# CM5_Adapter.net
KiCad netlist of a schematic drawn in Altium Designer
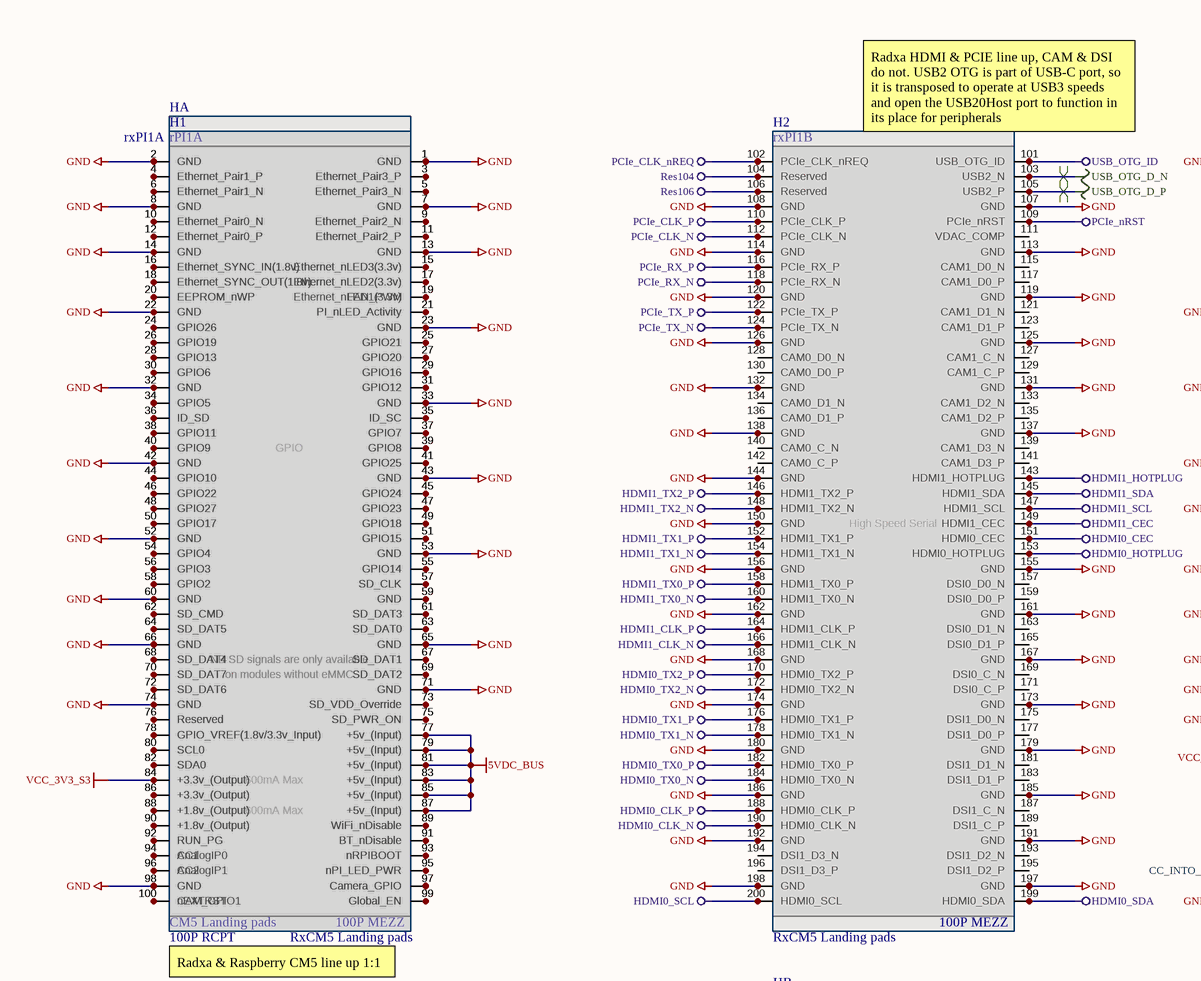
[diagram p0: CM5 Adapter.SchDoc, top left]
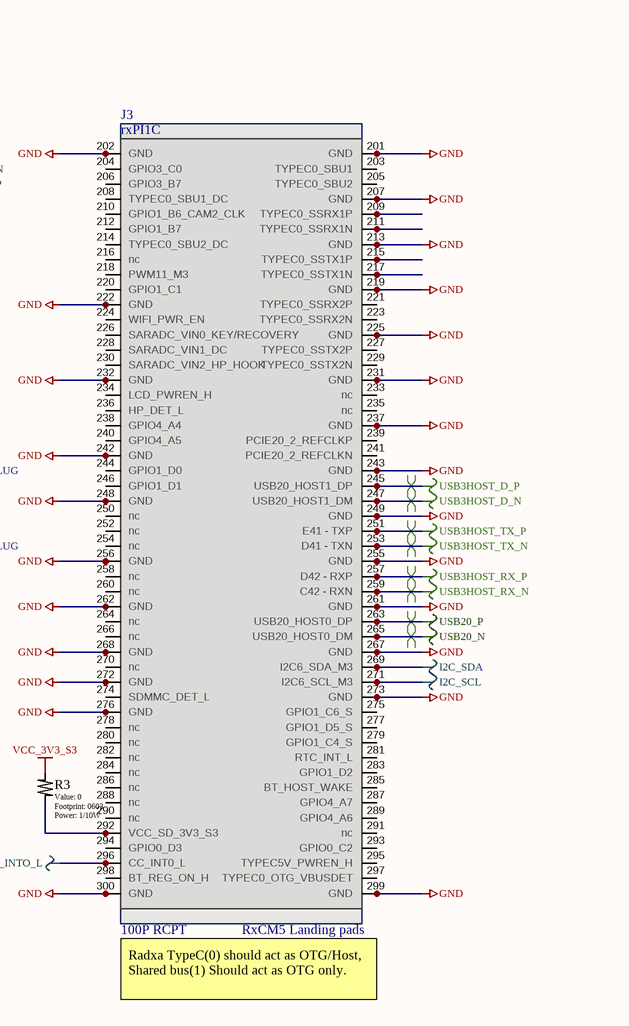
[diagram p1: CM5 Adapter.SchDoc, top right]
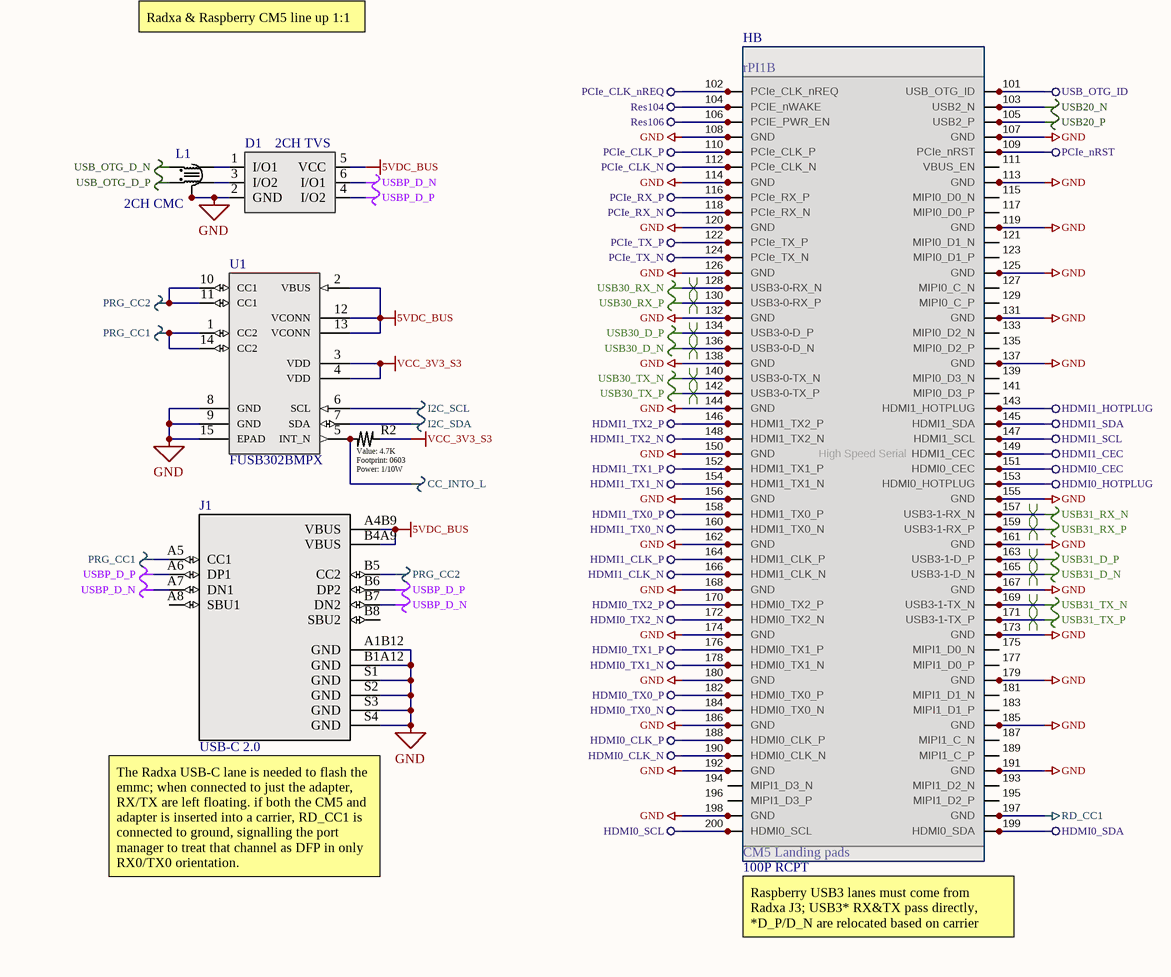
[diagram p2: CM5 Adapter.SchDoc, bottom left]
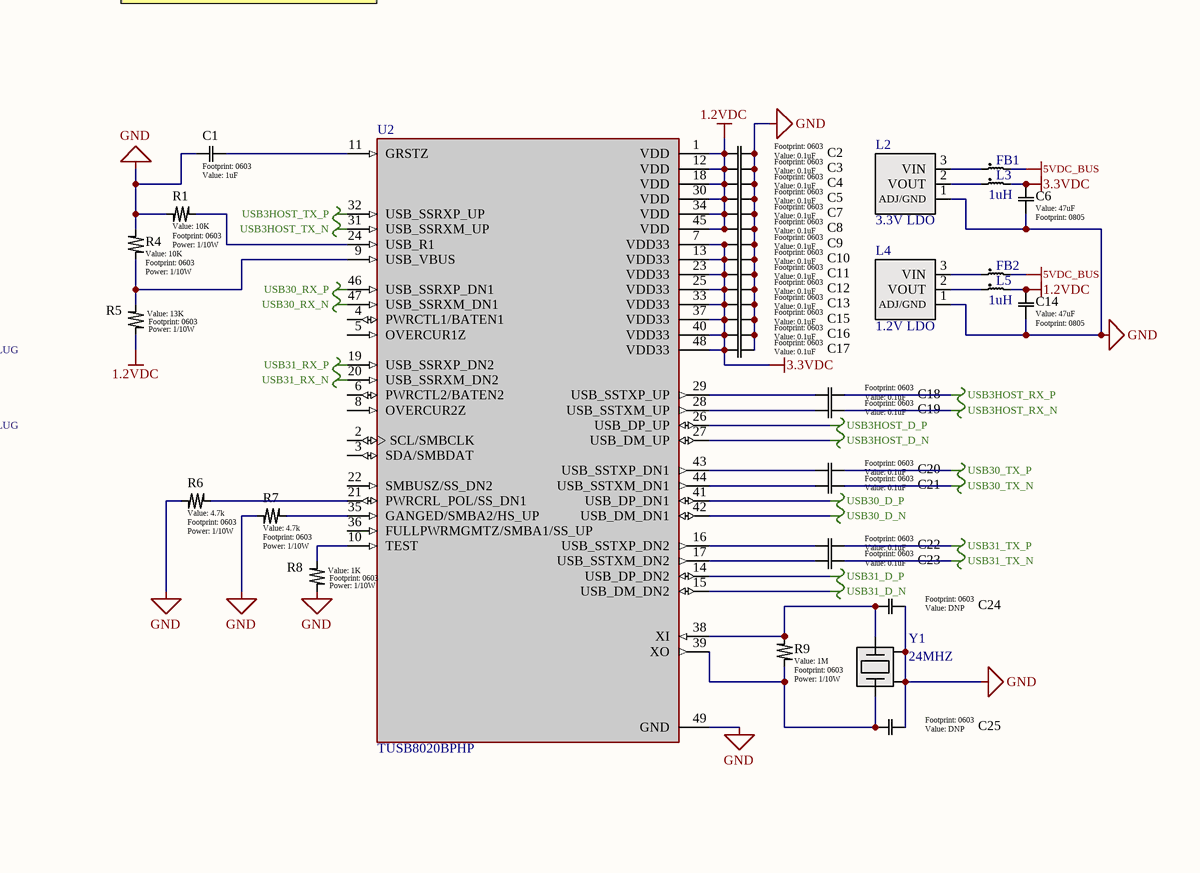
[diagram p3: CM5 Adapter.SchDoc, bottom right]

(export (version "E")
  (design (tool "Eeschema 10.0.6"))
  (components
    (comp (ref "C1")
      (value "1uF")
      (footprint "0603")
      (fields
        (field (name "VOLTAGE") ">10V")
        (field (name "TOLERANCE") "10%")
        (field (name "Comment") "Generic Capacitor")
      )
      (libsource (lib "Capacitors") (part "Generic Capacitor"))
    )
    (comp (ref "C2")
      (value "0.1uF")
      (footprint "0603")
      (fields
        (field (name "VOLTAGE") "10V")
        (field (name "TOLERANCE") "10%")
        (field (name "Comment") "Generic Capacitor")
      )
      (libsource (lib "Capacitors") (part "Generic Capacitor"))
    )
    (comp (ref "C3")
      (value "0.1uF")
      (footprint "0603")
      (fields
        (field (name "VOLTAGE") "10V")
        (field (name "TOLERANCE") "10%")
        (field (name "Comment") "Generic Capacitor")
      )
      (libsource (lib "Capacitors") (part "Generic Capacitor"))
    )
    (comp (ref "C4")
      (value "0.1uF")
      (footprint "0603")
      (fields
        (field (name "VOLTAGE") "10V")
        (field (name "TOLERANCE") "10%")
        (field (name "Comment") "Generic Capacitor")
      )
      (libsource (lib "Capacitors") (part "Generic Capacitor"))
    )
    (comp (ref "C5")
      (value "0.1uF")
      (footprint "0603")
      (fields
        (field (name "VOLTAGE") "10V")
        (field (name "TOLERANCE") "10%")
        (field (name "Comment") "Generic Capacitor")
      )
      (libsource (lib "Capacitors") (part "Generic Capacitor"))
    )
    (comp (ref "C6")
      (value "47uF")
      (footprint "0805")
      (fields
        (field (name "VOLTAGE") ">10V")
        (field (name "TOLERANCE") "10%")
        (field (name "Comment") "Generic Capacitor")
      )
      (libsource (lib "Capacitors") (part "Generic Capacitor"))
    )
    (comp (ref "C7")
      (value "0.1uF")
      (footprint "0603")
      (fields
        (field (name "VOLTAGE") "10V")
        (field (name "TOLERANCE") "10%")
        (field (name "Comment") "Generic Capacitor")
      )
      (libsource (lib "Capacitors") (part "Generic Capacitor"))
    )
    (comp (ref "C8")
      (value "0.1uF")
      (footprint "0603")
      (fields
        (field (name "VOLTAGE") "10V")
        (field (name "TOLERANCE") "10%")
        (field (name "Comment") "Generic Capacitor")
      )
      (libsource (lib "Capacitors") (part "Generic Capacitor"))
    )
    (comp (ref "C9")
      (value "0.1uF")
      (footprint "0603")
      (fields
        (field (name "VOLTAGE") "10V")
        (field (name "TOLERANCE") "10%")
        (field (name "Comment") "Generic Capacitor")
      )
      (libsource (lib "Capacitors") (part "Generic Capacitor"))
    )
    (comp (ref "C10")
      (value "0.1uF")
      (footprint "0603")
      (fields
        (field (name "VOLTAGE") "10V")
        (field (name "TOLERANCE") "10%")
        (field (name "Comment") "Generic Capacitor")
      )
      (libsource (lib "Capacitors") (part "Generic Capacitor"))
    )
    (comp (ref "C11")
      (value "0.1uF")
      (footprint "0603")
      (fields
        (field (name "VOLTAGE") "10V")
        (field (name "TOLERANCE") "10%")
        (field (name "Comment") "Generic Capacitor")
      )
      (libsource (lib "Capacitors") (part "Generic Capacitor"))
    )
    (comp (ref "C12")
      (value "0.1uF")
      (footprint "0603")
      (fields
        (field (name "VOLTAGE") "10V")
        (field (name "TOLERANCE") "10%")
        (field (name "Comment") "Generic Capacitor")
      )
      (libsource (lib "Capacitors") (part "Generic Capacitor"))
    )
    (comp (ref "C13")
      (value "0.1uF")
      (footprint "0603")
      (fields
        (field (name "VOLTAGE") "10V")
        (field (name "TOLERANCE") "10%")
        (field (name "Comment") "Generic Capacitor")
      )
      (libsource (lib "Capacitors") (part "Generic Capacitor"))
    )
    (comp (ref "C14")
      (value "47uF")
      (footprint "0805")
      (fields
        (field (name "VOLTAGE") ">10V")
        (field (name "TOLERANCE") "10%")
        (field (name "Comment") "Generic Capacitor")
      )
      (libsource (lib "Capacitors") (part "Generic Capacitor"))
    )
    (comp (ref "C15")
      (value "0.1uF")
      (footprint "0603")
      (fields
        (field (name "VOLTAGE") "10V")
        (field (name "TOLERANCE") "10%")
        (field (name "Comment") "Generic Capacitor")
      )
      (libsource (lib "Capacitors") (part "Generic Capacitor"))
    )
    (comp (ref "C16")
      (value "0.1uF")
      (footprint "0603")
      (fields
        (field (name "VOLTAGE") "10V")
        (field (name "TOLERANCE") "10%")
        (field (name "Comment") "Generic Capacitor")
      )
      (libsource (lib "Capacitors") (part "Generic Capacitor"))
    )
    (comp (ref "C17")
      (value "0.1uF")
      (footprint "0603")
      (fields
        (field (name "VOLTAGE") "10V")
        (field (name "TOLERANCE") "10%")
        (field (name "Comment") "Generic Capacitor")
      )
      (libsource (lib "Capacitors") (part "Generic Capacitor"))
    )
    (comp (ref "C18")
      (value "0.1uF")
      (footprint "0603")
      (fields
        (field (name "VOLTAGE") "10V")
        (field (name "TOLERANCE") "10%")
        (field (name "Comment") "Generic Capacitor")
      )
      (libsource (lib "Capacitors") (part "Generic Capacitor"))
    )
    (comp (ref "C19")
      (value "0.1uF")
      (footprint "0603")
      (fields
        (field (name "VOLTAGE") "10V")
        (field (name "TOLERANCE") "10%")
        (field (name "Comment") "Generic Capacitor")
      )
      (libsource (lib "Capacitors") (part "Generic Capacitor"))
    )
    (comp (ref "C20")
      (value "0.1uF")
      (footprint "0603")
      (fields
        (field (name "VOLTAGE") "10V")
        (field (name "TOLERANCE") "10%")
        (field (name "Comment") "Generic Capacitor")
      )
      (libsource (lib "Capacitors") (part "Generic Capacitor"))
    )
    (comp (ref "C21")
      (value "0.1uF")
      (footprint "0603")
      (fields
        (field (name "VOLTAGE") "10V")
        (field (name "TOLERANCE") "10%")
        (field (name "Comment") "Generic Capacitor")
      )
      (libsource (lib "Capacitors") (part "Generic Capacitor"))
    )
    (comp (ref "C22")
      (value "0.1uF")
      (footprint "0603")
      (fields
        (field (name "VOLTAGE") "10V")
        (field (name "TOLERANCE") "10%")
        (field (name "Comment") "Generic Capacitor")
      )
      (libsource (lib "Capacitors") (part "Generic Capacitor"))
    )
    (comp (ref "C23")
      (value "0.1uF")
      (footprint "0603")
      (fields
        (field (name "VOLTAGE") "10V")
        (field (name "TOLERANCE") "10%")
        (field (name "Comment") "Generic Capacitor")
      )
      (libsource (lib "Capacitors") (part "Generic Capacitor"))
    )
    (comp (ref "C24")
      (value "DNP")
      (footprint "0603")
      (fields
        (field (name "VOLTAGE") ">10V")
        (field (name "TOLERANCE") "10%")
        (field (name "Comment") "Generic Capacitor")
      )
      (libsource (lib "Capacitors") (part "Generic Capacitor"))
    )
    (comp (ref "C25")
      (value "DNP")
      (footprint "0603")
      (fields
        (field (name "VOLTAGE") ">10V")
        (field (name "TOLERANCE") "10%")
        (field (name "Comment") "Generic Capacitor")
      )
      (libsource (lib "Capacitors") (part "Generic Capacitor"))
    )
    (comp (ref "D1")
      (value "2CH TVS")
      (footprint "FP-SOT886-MFG")
      (description "TVS DIODE 5.5V 6XSON SOT886")
      (fields
        (field (name "OCTOPART") "https://octopart.com/prtr5v0u2f%2C115-nexperia-78741690")
        (field (name "MANUFACTURER") "Nexperia")
      )
      (libsource (lib "Diodes") (part "PRTR5V0U2F,115"))
    )
    (comp (ref "FB1")
      (value "BLM21PG221SN1D")
      (footprint "0805")
      (description "220 Ohms @ 100 MHz 1 Power Line Ferrite Bead 0805 (2012 Metric) 2A 45mOhm")
      (fields (field (name "MANUFACTURER") "Murata") (field (name "TOLERANCE") "25%"))
      (libsource (lib "Inductors") (part "BLM21PG221SN1D"))
    )
    (comp (ref "FB2")
      (value "BLM21PG221SN1D")
      (footprint "0805")
      (description "220 Ohms @ 100 MHz 1 Power Line Ferrite Bead 0805 (2012 Metric) 2A 45mOhm")
      (fields (field (name "MANUFACTURER") "Murata") (field (name "TOLERANCE") "25%"))
      (libsource (lib "Inductors") (part "BLM21PG221SN1D"))
    )
    (comp (ref "H1")
      (value "100P RCPT")
      (footprint "DF40C-100DS-0.4V(51)")
      (description "100 Position Connector Receptacle, Center Strip Contacts Surface Mount Gold")
      (fields (field (name "MF") "Hirose") (field (name "MP") "DF40C-100DS-0.4V(51)"))
      (libsource (lib "Connectors") (part "DF40-100DS RCPT_1"))
    )
    (comp (ref "H2")
      (value "100P MEZZ")
      (footprint "DF40C-100DS-0.4V(51)")
      (description "100 Position Connector Receptacle, Center Strip Contacts Surface Mount Gold")
      (fields (field (name "MF") "Hirose") (field (name "MP") "DF40C-100DS-0.4V(51)"))
      (libsource (lib "Connectors") (part "DF40-100DS RCPT_1"))
    )
    (comp (ref "HA")
      (value "100P MEZZ")
      (footprint "DF40C-100DP-0.4V(51)")
      (description "100 Position Connector Receptacle, Center Strip Contacts Surface Mount Gold")
      (fields (field (name "MF") "Hirose") (field (name "MP") "DF40C-100DS-0.4V(51)"))
      (libsource (lib "SOC_Carrier") (part "DF40-XX-100DS RCPT"))
    )
    (comp (ref "HB")
      (value "100P RCPT")
      (footprint "DF40C-100DP-0.4V(51)")
      (description "100 Position Connector Receptacle, Center Strip Contacts Surface Mount Gold")
      (fields (field (name "MF") "Hirose") (field (name "MP") "DF40C-100DS-0.4V(51)"))
      (libsource (lib "SOC_Carrier") (part "DF40-XX-100DS RCPT"))
    )
    (comp (ref "J1")
      (value "USB-C 2.0")
      (footprint "GT-USB-7010ASV")
      (libsource (lib "Connectors") (part "12402012E212A"))
    )
    (comp (ref "J3")
      (value "100P RCPT")
      (footprint "DF40C-100DS-0.4V(51)")
      (description "100 Position Connector Receptacle, Center Strip Contacts Surface Mount Gold")
      (fields (field (name "MF") "Hirose") (field (name "MP") "DF40C-100DS-0.4V(51)"))
      (libsource (lib "") (part "DF40-100DS RCPT_1_1"))
    )
    (comp (ref "L1")
      (value "2CH CMC")
      (footprint "SMD-6-2CH")
      (description "35Ω@100MHz -40℃~+85℃ 4Ω 5V 2 100mA SMD Common Mode Filters ROHS")
      (libsource (lib "Inductors") (part "ICMEF112P350MFR"))
    )
    (comp (ref "L2")
      (value "3.3V LDO")
      (footprint "SOT-223-3")
      (description "80dB@(120Hz) 1A Fixed 3.3V~3.3V Positive 18V SOT-223 Linear Voltage Regulator")
      (libsource (lib "Regulators") (part "ZLDO1117QG33TA"))
    )
    (comp (ref "L3")
      (value "1uH")
      (footprint "0806")
      (description "1µH Shielded Fixed Inductor 59mOhm Max 0806 (2016 Metric) -")
      (libsource (lib "Inductors") (part "HMLQ20161T-1R0MDR"))
    )
    (comp (ref "L4")
      (value "1.2V LDO")
      (footprint "SOT-223-3")
      (description "1A Fixed 1.2V Positive 20V SOT-223 Linear Voltage Regulator")
      (libsource (lib "Regulators") (part "SSP1117-1.2V"))
    )
    (comp (ref "L5")
      (value "1uH")
      (footprint "0806")
      (description "1µH Shielded Fixed Inductor 59mOhm Max 0806 (2016 Metric) -")
      (libsource (lib "Inductors") (part "HMLQ20161T-1R0MDR"))
    )
    (comp (ref "R1")
      (value "10K")
      (footprint "0603")
      (fields
        (field (name "TOLERANCE") "1%")
        (field (name "POWER") "1/10W")
        (field (name "Comment") "Generic Resistor")
      )
      (libsource (lib "Resistors") (part "Generic Resistor"))
    )
    (comp (ref "R2")
      (value "4.7K")
      (footprint "0603")
      (fields
        (field (name "TOLERANCE") "1%")
        (field (name "POWER") "1/10W")
        (field (name "Comment") "Generic Resistor")
      )
      (libsource (lib "Resistors") (part "Generic Resistor"))
    )
    (comp (ref "R3")
      (value "0")
      (footprint "0603")
      (fields
        (field (name "TOLERANCE") "1%")
        (field (name "POWER") "1/10W")
        (field (name "Comment") "Generic Resistor")
      )
      (libsource (lib "Resistors") (part "Generic Resistor"))
    )
    (comp (ref "R4")
      (value "10K")
      (footprint "0603")
      (fields
        (field (name "TOLERANCE") "1%")
        (field (name "POWER") "1/10W")
        (field (name "Comment") "Generic Resistor")
      )
      (libsource (lib "Resistors") (part "Generic Resistor"))
    )
    (comp (ref "R5")
      (value "13K")
      (footprint "0603")
      (fields
        (field (name "TOLERANCE") "1%")
        (field (name "POWER") "1/10W")
        (field (name "Comment") "Generic Resistor")
      )
      (libsource (lib "Resistors") (part "Generic Resistor"))
    )
    (comp (ref "R6")
      (value "4.7k")
      (footprint "0603")
      (fields
        (field (name "TOLERANCE") "1%")
        (field (name "POWER") "1/10W")
        (field (name "Comment") "Generic Resistor")
      )
      (libsource (lib "Resistors") (part "Generic Resistor"))
    )
    (comp (ref "R7")
      (value "4.7k")
      (footprint "0603")
      (fields
        (field (name "TOLERANCE") "1%")
        (field (name "POWER") "1/10W")
        (field (name "Comment") "Generic Resistor")
      )
      (libsource (lib "Resistors") (part "Generic Resistor"))
    )
    (comp (ref "R8")
      (value "1K")
      (footprint "0603")
      (fields
        (field (name "TOLERANCE") "1%")
        (field (name "POWER") "1/10W")
        (field (name "Comment") "Generic Resistor")
      )
      (libsource (lib "Resistors") (part "Generic Resistor"))
    )
    (comp (ref "R9")
      (value "1M")
      (footprint "0603")
      (fields
        (field (name "TOLERANCE") "1%")
        (field (name "POWER") "1/10W")
        (field (name "Comment") "Generic Resistor")
      )
      (libsource (lib "Resistors") (part "Generic Resistor"))
    )
    (comp (ref "rPI1")
      (value "CM5 Landing pads")
      (footprint "rP-200P-CM-REP (top)")
      (libsource (lib "SOC_Carrier") (part "RP-CM5-Rep"))
    )
    (comp (ref "rxPI1")
      (value "RxCM5 Landing pads")
      (footprint "RX-300P-CM-FTPD")
      (libsource (lib "SOC_Carrier") (part "RX-CM5"))
    )
    (comp (ref "U1")
      (value "FUSB302BMPX")
      (footprint "MLP14_2P5X2P5_ONS-L")
      (description "IC USB TYPE C CTLR PROGR 14-MLP")
      (fields (field (name "COPYRIGHT") "Copyright (C) 2025 Ultra Librarian. All rights reserved."))
      (libsource (lib "Misc ICs") (part "FUSB302BMPX"))
    )
    (comp (ref "U2")
      (value "TUSB8020BPHP")
      (footprint "HTQFP-48(7x7)")
      (description "USB Hub Controller USB 3.0")
      (libsource (lib "Misc ICs") (part "TUSB8020BPHP"))
    )
    (comp (ref "Y1")
      (value "24MHZ")
      (footprint "SMD2520-4P")
      (description "24MHz 20pF ±10ppm ±30ppm SMD-2520-4P Crystals ROHS")
      (libsource (lib "Clock ICs") (part "CM4024M00020001"))
    )
  )
  (nets
    (net (code "1") (name "1.2VDC") (class "Default")
      (node (ref "C14") (pin "1") (pinfunction "1_1") (pintype "passive"))
      (node (ref "C2") (pin "2") (pinfunction "2_2") (pintype "passive"))
      (node (ref "C3") (pin "2") (pinfunction "2_2") (pintype "passive"))
      (node (ref "C4") (pin "2") (pinfunction "2_2") (pintype "passive"))
      (node (ref "C5") (pin "2") (pinfunction "2_2") (pintype "passive"))
      (node (ref "C7") (pin "2") (pinfunction "2_2") (pintype "passive"))
      (node (ref "C8") (pin "2") (pinfunction "2_2") (pintype "passive"))
      (node (ref "L5") (pin "2") (pinfunction "2_2") (pintype "passive"))
      (node (ref "R5") (pin "1") (pinfunction "1_1") (pintype "passive"))
      (node (ref "U2") (pin "1") (pinfunction "VDD_1") (pintype "power_in"))
      (node (ref "U2") (pin "12") (pinfunction "VDD_12") (pintype "power_in"))
      (node (ref "U2") (pin "18") (pinfunction "VDD_18") (pintype "power_in"))
      (node (ref "U2") (pin "30") (pinfunction "VDD_30") (pintype "power_in"))
      (node (ref "U2") (pin "34") (pinfunction "VDD_34") (pintype "power_in"))
      (node (ref "U2") (pin "45") (pinfunction "VDD_45") (pintype "power_in"))
    )
    (net (code "2") (name "3.3VDC") (class "Default")
      (node (ref "C10") (pin "2") (pinfunction "2_2") (pintype "passive"))
      (node (ref "C11") (pin "2") (pinfunction "2_2") (pintype "passive"))
      (node (ref "C12") (pin "2") (pinfunction "2_2") (pintype "passive"))
      (node (ref "C13") (pin "2") (pinfunction "2_2") (pintype "passive"))
      (node (ref "C15") (pin "2") (pinfunction "2_2") (pintype "passive"))
      (node (ref "C16") (pin "2") (pinfunction "2_2") (pintype "passive"))
      (node (ref "C17") (pin "2") (pinfunction "2_2") (pintype "passive"))
      (node (ref "C6") (pin "1") (pinfunction "1_1") (pintype "passive"))
      (node (ref "C9") (pin "2") (pinfunction "2_2") (pintype "passive"))
      (node (ref "L3") (pin "2") (pinfunction "2_2") (pintype "passive"))
      (node (ref "U2") (pin "13") (pinfunction "VDD33_13") (pintype "power_in"))
      (node (ref "U2") (pin "23") (pinfunction "VDD33_23") (pintype "power_in"))
      (node (ref "U2") (pin "25") (pinfunction "VDD33_25") (pintype "power_in"))
      (node (ref "U2") (pin "33") (pinfunction "VDD33_33") (pintype "power_in"))
      (node (ref "U2") (pin "37") (pinfunction "VDD33_37") (pintype "power_in"))
      (node (ref "U2") (pin "40") (pinfunction "VDD33_40") (pintype "power_in"))
      (node (ref "U2") (pin "48") (pinfunction "VDD33_48") (pintype "power_in"))
      (node (ref "U2") (pin "7") (pinfunction "VDD33_7") (pintype "power_in"))
    )
    (net (code "3") (name "5VDC_BUS") (class "Default")
      (node (ref "D1") (pin "5") (pinfunction "VCC_5") (pintype "power_in"))
      (node (ref "FB1") (pin "2") (pinfunction "2_2") (pintype "passive"))
      (node (ref "FB2") (pin "2") (pinfunction "2_2") (pintype "passive"))
      (node (ref "H1") (pin "77") (pinfunction "77_77") (pintype "passive"))
      (node (ref "H1") (pin "79") (pinfunction "79_79") (pintype "passive"))
      (node (ref "H1") (pin "81") (pinfunction "81_81") (pintype "passive"))
      (node (ref "H1") (pin "83") (pinfunction "83_83") (pintype "passive"))
      (node (ref "H1") (pin "85") (pinfunction "85_85") (pintype "passive"))
      (node (ref "H1") (pin "87") (pinfunction "87_87") (pintype "passive"))
      (node (ref "HA") (pin "78") (pinfunction "78_78") (pintype "passive"))
      (node (ref "HA") (pin "80") (pinfunction "80_80") (pintype "passive"))
      (node (ref "HA") (pin "82") (pinfunction "82_82") (pintype "passive"))
      (node (ref "HA") (pin "84") (pinfunction "84_84") (pintype "passive"))
      (node (ref "HA") (pin "86") (pinfunction "86_86") (pintype "passive"))
      (node (ref "HA") (pin "88") (pinfunction "88_88") (pintype "passive"))
      (node (ref "J1") (pin "A4B9") (pinfunction "VBUS_A4B9") (pintype "power_in"))
      (node (ref "J1") (pin "B4A9") (pinfunction "VBUS_B4A9") (pintype "power_in"))
      (node (ref "U1") (pin "12") (pinfunction "VCONN_12") (pintype "power_in"))
      (node (ref "U1") (pin "13") (pinfunction "VCONN_13") (pintype "power_in"))
      (node (ref "U1") (pin "2") (pinfunction "VBUS_2") (pintype "input"))
      (node (ref "rPI1") (pin "77") (pinfunction "+5v_(Input)_77") (pintype "passive"))
      (node (ref "rPI1") (pin "79") (pinfunction "+5v_(Input)_79") (pintype "passive"))
      (node (ref "rPI1") (pin "81") (pinfunction "+5v_(Input)_81") (pintype "passive"))
      (node (ref "rPI1") (pin "83") (pinfunction "+5v_(Input)_83") (pintype "passive"))
      (node (ref "rPI1") (pin "85") (pinfunction "+5v_(Input)_85") (pintype "passive"))
      (node (ref "rPI1") (pin "87") (pinfunction "+5v_(Input)_87") (pintype "passive"))
      (node (ref "rxPI1") (pin "77") (pinfunction "+5v_(Input)_77") (pintype "passive"))
      (node (ref "rxPI1") (pin "79") (pinfunction "+5v_(Input)_79") (pintype "passive"))
      (node (ref "rxPI1") (pin "81") (pinfunction "+5v_(Input)_81") (pintype "passive"))
      (node (ref "rxPI1") (pin "83") (pinfunction "+5v_(Input)_83") (pintype "passive"))
      (node (ref "rxPI1") (pin "85") (pinfunction "+5v_(Input)_85") (pintype "passive"))
      (node (ref "rxPI1") (pin "87") (pinfunction "+5v_(Input)_87") (pintype "passive"))
    )
    (net (code "4") (name "CC_INTO_L") (class "Default")
      (node (ref "J3") (pin "95") (pinfunction "95_95") (pintype "passive"))
      (node (ref "R2") (pin "1") (pinfunction "1_1") (pintype "passive"))
      (node (ref "U1") (pin "5") (pinfunction "INT_N_5") (pintype "output"))
      (node (ref "rxPI1") (pin "296") (pinfunction "CC_INT0_L_296") (pintype "passive"))
    )
    (net (code "5") (name "GND") (class "Default")
      (node (ref "C1") (pin "1") (pinfunction "1_1") (pintype "passive"))
      (node (ref "C10") (pin "1") (pinfunction "1_1") (pintype "passive"))
      (node (ref "C11") (pin "1") (pinfunction "1_1") (pintype "passive"))
      (node (ref "C12") (pin "1") (pinfunction "1_1") (pintype "passive"))
      (node (ref "C13") (pin "1") (pinfunction "1_1") (pintype "passive"))
      (node (ref "C14") (pin "2") (pinfunction "2_2") (pintype "passive"))
      (node (ref "C15") (pin "1") (pinfunction "1_1") (pintype "passive"))
      (node (ref "C16") (pin "1") (pinfunction "1_1") (pintype "passive"))
      (node (ref "C17") (pin "1") (pinfunction "1_1") (pintype "passive"))
      (node (ref "C2") (pin "1") (pinfunction "1_1") (pintype "passive"))
      (node (ref "C24") (pin "1") (pinfunction "1_1") (pintype "passive"))
      (node (ref "C25") (pin "1") (pinfunction "1_1") (pintype "passive"))
      (node (ref "C3") (pin "1") (pinfunction "1_1") (pintype "passive"))
      (node (ref "C4") (pin "1") (pinfunction "1_1") (pintype "passive"))
      (node (ref "C5") (pin "1") (pinfunction "1_1") (pintype "passive"))
      (node (ref "C6") (pin "2") (pinfunction "2_2") (pintype "passive"))
      (node (ref "C7") (pin "1") (pinfunction "1_1") (pintype "passive"))
      (node (ref "C8") (pin "1") (pinfunction "1_1") (pintype "passive"))
      (node (ref "C9") (pin "1") (pinfunction "1_1") (pintype "passive"))
      (node (ref "D1") (pin "2") (pinfunction "GND_2") (pintype "power_in"))
      (node (ref "H1") (pin "1") (pinfunction "1_1") (pintype "passive"))
      (node (ref "H1") (pin "13") (pinfunction "13_13") (pintype "passive"))
      (node (ref "H1") (pin "14") (pinfunction "14_14") (pintype "passive"))
      (node (ref "H1") (pin "2") (pinfunction "2_2") (pintype "passive"))
      (node (ref "H1") (pin "22") (pinfunction "22_22") (pintype "passive"))
      (node (ref "H1") (pin "23") (pinfunction "23_23") (pintype "passive"))
      (node (ref "H1") (pin "32") (pinfunction "32_32") (pintype "passive"))
      (node (ref "H1") (pin "33") (pinfunction "33_33") (pintype "passive"))
      (node (ref "H1") (pin "42") (pinfunction "42_42") (pintype "passive"))
      (node (ref "H1") (pin "43") (pinfunction "43_43") (pintype "passive"))
      (node (ref "H1") (pin "52") (pinfunction "52_52") (pintype "passive"))
      (node (ref "H1") (pin "53") (pinfunction "53_53") (pintype "passive"))
      (node (ref "H1") (pin "60") (pinfunction "60_60") (pintype "passive"))
      (node (ref "H1") (pin "65") (pinfunction "65_65") (pintype "passive"))
      (node (ref "H1") (pin "66") (pinfunction "66_66") (pintype "passive"))
      (node (ref "H1") (pin "7") (pinfunction "7_7") (pintype "passive"))
      (node (ref "H1") (pin "71") (pinfunction "71_71") (pintype "passive"))
      (node (ref "H1") (pin "74") (pinfunction "74_74") (pintype "passive"))
      (node (ref "H1") (pin "8") (pinfunction "8_8") (pintype "passive"))
      (node (ref "H1") (pin "98") (pinfunction "98_98") (pintype "passive"))
      (node (ref "H2") (pin "13") (pinfunction "13_13") (pintype "passive"))
      (node (ref "H2") (pin "14") (pinfunction "14_14") (pintype "passive"))
      (node (ref "H2") (pin "19") (pinfunction "19_19") (pintype "passive"))
      (node (ref "H2") (pin "20") (pinfunction "20_20") (pintype "passive"))
      (node (ref "H2") (pin "25") (pinfunction "25_25") (pintype "passive"))
      (node (ref "H2") (pin "26") (pinfunction "26_26") (pintype "passive"))
      (node (ref "H2") (pin "31") (pinfunction "31_31") (pintype "passive"))
      (node (ref "H2") (pin "32") (pinfunction "32_32") (pintype "passive"))
      (node (ref "H2") (pin "37") (pinfunction "37_37") (pintype "passive"))
      (node (ref "H2") (pin "38") (pinfunction "38_38") (pintype "passive"))
      (node (ref "H2") (pin "44") (pinfunction "44_44") (pintype "passive"))
      (node (ref "H2") (pin "50") (pinfunction "50_50") (pintype "passive"))
      (node (ref "H2") (pin "55") (pinfunction "55_55") (pintype "passive"))
      (node (ref "H2") (pin "56") (pinfunction "56_56") (pintype "passive"))
      (node (ref "H2") (pin "61") (pinfunction "61_61") (pintype "passive"))
      (node (ref "H2") (pin "62") (pinfunction "62_62") (pintype "passive"))
      (node (ref "H2") (pin "67") (pinfunction "67_67") (pintype "passive"))
      (node (ref "H2") (pin "68") (pinfunction "68_68") (pintype "passive"))
      (node (ref "H2") (pin "7") (pinfunction "7_7") (pintype "passive"))
      (node (ref "H2") (pin "73") (pinfunction "73_73") (pintype "passive"))
      (node (ref "H2") (pin "74") (pinfunction "74_74") (pintype "passive"))
      (node (ref "H2") (pin "79") (pinfunction "79_79") (pintype "passive"))
      (node (ref "H2") (pin "8") (pinfunction "8_8") (pintype "passive"))
      (node (ref "H2") (pin "80") (pinfunction "80_80") (pintype "passive"))
      (node (ref "H2") (pin "85") (pinfunction "85_85") (pintype "passive"))
      (node (ref "H2") (pin "86") (pinfunction "86_86") (pintype "passive"))
      (node (ref "H2") (pin "91") (pinfunction "91_91") (pintype "passive"))
      (node (ref "H2") (pin "92") (pinfunction "92_92") (pintype "passive"))
      (node (ref "H2") (pin "97") (pinfunction "97_97") (pintype "passive"))
      (node (ref "H2") (pin "98") (pinfunction "98_98") (pintype "passive"))
      (node (ref "HA") (pin "1") (pinfunction "1_1") (pintype "passive"))
      (node (ref "HA") (pin "13") (pinfunction "13_13") (pintype "passive"))
      (node (ref "HA") (pin "14") (pinfunction "14_14") (pintype "passive"))
      (node (ref "HA") (pin "2") (pinfunction "2_2") (pintype "passive"))
      (node (ref "HA") (pin "21") (pinfunction "21_21") (pintype "passive"))
      (node (ref "HA") (pin "24") (pinfunction "24_24") (pintype "passive"))
      (node (ref "HA") (pin "31") (pinfunction "31_31") (pintype "passive"))
      (node (ref "HA") (pin "34") (pinfunction "34_34") (pintype "passive"))
      (node (ref "HA") (pin "41") (pinfunction "41_41") (pintype "passive"))
      (node (ref "HA") (pin "44") (pinfunction "44_44") (pintype "passive"))
      (node (ref "HA") (pin "51") (pinfunction "51_51") (pintype "passive"))
      (node (ref "HA") (pin "54") (pinfunction "54_54") (pintype "passive"))
      (node (ref "HA") (pin "59") (pinfunction "59_59") (pintype "passive"))
      (node (ref "HA") (pin "65") (pinfunction "65_65") (pintype "passive"))
      (node (ref "HA") (pin "66") (pinfunction "66_66") (pintype "passive"))
      (node (ref "HA") (pin "7") (pinfunction "7_7") (pintype "passive"))
      (node (ref "HA") (pin "72") (pinfunction "72_72") (pintype "passive"))
      (node (ref "HA") (pin "73") (pinfunction "73_73") (pintype "passive"))
      (node (ref "HA") (pin "8") (pinfunction "8_8") (pintype "passive"))
      (node (ref "HA") (pin "97") (pinfunction "97_97") (pintype "passive"))
      (node (ref "HB") (pin "13") (pinfunction "13_13") (pintype "passive"))
      (node (ref "HB") (pin "14") (pinfunction "14_14") (pintype "passive"))
      (node (ref "HB") (pin "19") (pinfunction "19_19") (pintype "passive"))
      (node (ref "HB") (pin "20") (pinfunction "20_20") (pintype "passive"))
      (node (ref "HB") (pin "25") (pinfunction "25_25") (pintype "passive"))
      (node (ref "HB") (pin "26") (pinfunction "26_26") (pintype "passive"))
      (node (ref "HB") (pin "31") (pinfunction "31_31") (pintype "passive"))
      (node (ref "HB") (pin "32") (pinfunction "32_32") (pintype "passive"))
      (node (ref "HB") (pin "37") (pinfunction "37_37") (pintype "passive"))
      (node (ref "HB") (pin "38") (pinfunction "38_38") (pintype "passive"))
      (node (ref "HB") (pin "43") (pinfunction "43_43") (pintype "passive"))
      (node (ref "HB") (pin "49") (pinfunction "49_49") (pintype "passive"))
      (node (ref "HB") (pin "55") (pinfunction "55_55") (pintype "passive"))
      (node (ref "HB") (pin "56") (pinfunction "56_56") (pintype "passive"))
      (node (ref "HB") (pin "61") (pinfunction "61_61") (pintype "passive"))
      (node (ref "HB") (pin "62") (pinfunction "62_62") (pintype "passive"))
      (node (ref "HB") (pin "67") (pinfunction "67_67") (pintype "passive"))
      (node (ref "HB") (pin "68") (pinfunction "68_68") (pintype "passive"))
      (node (ref "HB") (pin "7") (pinfunction "7_7") (pintype "passive"))
      (node (ref "HB") (pin "73") (pinfunction "73_73") (pintype "passive"))
      (node (ref "HB") (pin "74") (pinfunction "74_74") (pintype "passive"))
      (node (ref "HB") (pin "79") (pinfunction "79_79") (pintype "passive"))
      (node (ref "HB") (pin "8") (pinfunction "8_8") (pintype "passive"))
      (node (ref "HB") (pin "80") (pinfunction "80_80") (pintype "passive"))
      (node (ref "HB") (pin "85") (pinfunction "85_85") (pintype "passive"))
      (node (ref "HB") (pin "86") (pinfunction "86_86") (pintype "passive"))
      (node (ref "HB") (pin "91") (pinfunction "91_91") (pintype "passive"))
      (node (ref "HB") (pin "92") (pinfunction "92_92") (pintype "passive"))
      (node (ref "HB") (pin "97") (pinfunction "97_97") (pintype "passive"))
      (node (ref "J1") (pin "A1B12") (pinfunction "GND_A1B12") (pintype "power_in"))
      (node (ref "J1") (pin "B1A12") (pinfunction "GND_B1A12") (pintype "power_in"))
      (node (ref "J1") (pin "S1") (pinfunction "GND_S1") (pintype "power_in"))
      (node (ref "J1") (pin "S2") (pinfunction "GND_S2") (pintype "power_in"))
      (node (ref "J1") (pin "S3") (pinfunction "GND_S3") (pintype "power_in"))
      (node (ref "J1") (pin "S4") (pinfunction "GND_S4") (pintype "power_in"))
      (node (ref "J3") (pin "1") (pinfunction "1_1") (pintype "passive"))
      (node (ref "J3") (pin "100") (pinfunction "100_100") (pintype "passive"))
      (node (ref "J3") (pin "14") (pinfunction "14_14") (pintype "passive"))
      (node (ref "J3") (pin "2") (pinfunction "2_2") (pintype "passive"))
      (node (ref "J3") (pin "20") (pinfunction "20_20") (pintype "passive"))
      (node (ref "J3") (pin "21") (pinfunction "21_21") (pintype "passive"))
      (node (ref "J3") (pin "26") (pinfunction "26_26") (pintype "passive"))
      (node (ref "J3") (pin "31") (pinfunction "31_31") (pintype "passive"))
      (node (ref "J3") (pin "32") (pinfunction "32_32") (pintype "passive"))
      (node (ref "J3") (pin "38") (pinfunction "38_38") (pintype "passive"))
      (node (ref "J3") (pin "41") (pinfunction "41_41") (pintype "passive"))
      (node (ref "J3") (pin "44") (pinfunction "44_44") (pintype "passive"))
      (node (ref "J3") (pin "47") (pinfunction "47_47") (pintype "passive"))
      (node (ref "J3") (pin "50") (pinfunction "50_50") (pintype "passive"))
      (node (ref "J3") (pin "55") (pinfunction "55_55") (pintype "passive"))
      (node (ref "J3") (pin "56") (pinfunction "56_56") (pintype "passive"))
      (node (ref "J3") (pin "61") (pinfunction "61_61") (pintype "passive"))
      (node (ref "J3") (pin "62") (pinfunction "62_62") (pintype "passive"))
      (node (ref "J3") (pin "67") (pinfunction "67_67") (pintype "passive"))
      (node (ref "J3") (pin "68") (pinfunction "68_68") (pintype "passive"))
      (node (ref "J3") (pin "71") (pinfunction "71_71") (pintype "passive"))
      (node (ref "J3") (pin "74") (pinfunction "74_74") (pintype "passive"))
      (node (ref "J3") (pin "75") (pinfunction "75_75") (pintype "passive"))
      (node (ref "J3") (pin "8") (pinfunction "8_8") (pintype "passive"))
      (node (ref "J3") (pin "99") (pinfunction "99_99") (pintype "passive"))
      (node (ref "L1") (pin "5") (pinfunction "5_5") (pintype "passive"))
      (node (ref "L1") (pin "6") (pinfunction "6_6") (pintype "passive"))
      (node (ref "L2") (pin "1") (pinfunction "ADJ/GND_1") (pintype "passive"))
      (node (ref "L4") (pin "1") (pinfunction "ADJ/GND_1") (pintype "passive"))
      (node (ref "R1") (pin "1") (pinfunction "1_1") (pintype "passive"))
      (node (ref "R4") (pin "1") (pinfunction "1_1") (pintype "passive"))
      (node (ref "R6") (pin "1") (pinfunction "1_1") (pintype "passive"))
      (node (ref "R7") (pin "1") (pinfunction "1_1") (pintype "passive"))
      (node (ref "R8") (pin "1") (pinfunction "1_1") (pintype "passive"))
      (node (ref "U1") (pin "15") (pinfunction "EPAD_15") (pintype "passive"))
      (node (ref "U1") (pin "8") (pinfunction "GND_8") (pintype "power_in"))
      (node (ref "U1") (pin "9") (pinfunction "GND_9") (pintype "power_in"))
      (node (ref "U2") (pin "49") (pinfunction "GND_49") (pintype "power_in"))
      (node (ref "Y1") (pin "2") (pinfunction "GND_2") (pintype "power_in"))
      (node (ref "Y1") (pin "4") (pinfunction "GND_4") (pintype "power_in"))
      (node (ref "rPI1") (pin "1") (pinfunction "GND_1") (pintype "passive"))
      (node (ref "rPI1") (pin "107") (pinfunction "GND_107") (pintype "passive"))
      (node (ref "rPI1") (pin "108") (pinfunction "GND_108") (pintype "passive"))
      (node (ref "rPI1") (pin "113") (pinfunction "GND_113") (pintype "passive"))
      (node (ref "rPI1") (pin "114") (pinfunction "GND_114") (pintype "passive"))
      (node (ref "rPI1") (pin "119") (pinfunction "GND_119") (pintype "passive"))
      (node (ref "rPI1") (pin "120") (pinfunction "GND_120") (pintype "passive"))
      (node (ref "rPI1") (pin "125") (pinfunction "GND_125") (pintype "passive"))
      (node (ref "rPI1") (pin "126") (pinfunction "GND_126") (pintype "passive"))
      (node (ref "rPI1") (pin "13") (pinfunction "GND_13") (pintype "passive"))
      (node (ref "rPI1") (pin "131") (pinfunction "GND_131") (pintype "passive"))
      (node (ref "rPI1") (pin "132") (pinfunction "GND_132") (pintype "passive"))
      (node (ref "rPI1") (pin "137") (pinfunction "GND_137") (pintype "passive"))
      (node (ref "rPI1") (pin "138") (pinfunction "GND_138") (pintype "passive"))
      (node (ref "rPI1") (pin "14") (pinfunction "GND_14") (pintype "passive"))
      (node (ref "rPI1") (pin "144") (pinfunction "GND_144") (pintype "passive"))
      (node (ref "rPI1") (pin "150") (pinfunction "GND_150") (pintype "passive"))
      (node (ref "rPI1") (pin "155") (pinfunction "GND_155") (pintype "passive"))
      (node (ref "rPI1") (pin "156") (pinfunction "GND_156") (pintype "passive"))
      (node (ref "rPI1") (pin "161") (pinfunction "GND_161") (pintype "passive"))
      (node (ref "rPI1") (pin "162") (pinfunction "GND_162") (pintype "passive"))
      (node (ref "rPI1") (pin "167") (pinfunction "GND_167") (pintype "passive"))
      (node (ref "rPI1") (pin "168") (pinfunction "GND_168") (pintype "passive"))
      (node (ref "rPI1") (pin "173") (pinfunction "GND_173") (pintype "passive"))
      (node (ref "rPI1") (pin "174") (pinfunction "GND_174") (pintype "passive"))
      (node (ref "rPI1") (pin "179") (pinfunction "GND_179") (pintype "passive"))
      (node (ref "rPI1") (pin "180") (pinfunction "GND_180") (pintype "passive"))
      (node (ref "rPI1") (pin "185") (pinfunction "GND_185") (pintype "passive"))
      (node (ref "rPI1") (pin "186") (pinfunction "GND_186") (pintype "passive"))
      (node (ref "rPI1") (pin "191") (pinfunction "GND_191") (pintype "passive"))
      (node (ref "rPI1") (pin "192") (pinfunction "GND_192") (pintype "passive"))
      (node (ref "rPI1") (pin "198") (pinfunction "GND_198") (pintype "passive"))
      (node (ref "rPI1") (pin "2") (pinfunction "GND_2") (pintype "passive"))
      (node (ref "rPI1") (pin "22") (pinfunction "GND_22") (pintype "passive"))
      (node (ref "rPI1") (pin "23") (pinfunction "GND_23") (pintype "passive"))
      (node (ref "rPI1") (pin "32") (pinfunction "GND_32") (pintype "passive"))
      (node (ref "rPI1") (pin "33") (pinfunction "GND_33") (pintype "passive"))
      (node (ref "rPI1") (pin "42") (pinfunction "GND_42") (pintype "passive"))
      (node (ref "rPI1") (pin "43") (pinfunction "GND_43") (pintype "passive"))
      (node (ref "rPI1") (pin "52") (pinfunction "GND_52") (pintype "passive"))
      (node (ref "rPI1") (pin "53") (pinfunction "GND_53") (pintype "passive"))
      (node (ref "rPI1") (pin "60") (pinfunction "GND_60") (pintype "passive"))
      (node (ref "rPI1") (pin "65") (pinfunction "GND_65") (pintype "passive"))
      (node (ref "rPI1") (pin "66") (pinfunction "GND_66") (pintype "passive"))
      (node (ref "rPI1") (pin "7") (pinfunction "GND_7") (pintype "passive"))
      (node (ref "rPI1") (pin "71") (pinfunction "GND_71") (pintype "passive"))
      (node (ref "rPI1") (pin "74") (pinfunction "GND_74") (pintype "passive"))
      (node (ref "rPI1") (pin "8") (pinfunction "GND_8") (pintype "passive"))
      (node (ref "rPI1") (pin "98") (pinfunction "GND_98") (pintype "passive"))
      (node (ref "rxPI1") (pin "1") (pinfunction "GND_1") (pintype "passive"))
      (node (ref "rxPI1") (pin "107") (pinfunction "GND_107") (pintype "passive"))
      (node (ref "rxPI1") (pin "108") (pinfunction "GND_108") (pintype "passive"))
      (node (ref "rxPI1") (pin "113") (pinfunction "GND_113") (pintype "passive"))
      (node (ref "rxPI1") (pin "114") (pinfunction "GND_114") (pintype "passive"))
      (node (ref "rxPI1") (pin "119") (pinfunction "GND_119") (pintype "passive"))
      (node (ref "rxPI1") (pin "120") (pinfunction "GND_120") (pintype "passive"))
      (node (ref "rxPI1") (pin "125") (pinfunction "GND_125") (pintype "passive"))
      (node (ref "rxPI1") (pin "126") (pinfunction "GND_126") (pintype "passive"))
      (node (ref "rxPI1") (pin "13") (pinfunction "GND_13") (pintype "passive"))
      (node (ref "rxPI1") (pin "131") (pinfunction "GND_131") (pintype "passive"))
      (node (ref "rxPI1") (pin "132") (pinfunction "GND_132") (pintype "passive"))
      (node (ref "rxPI1") (pin "137") (pinfunction "GND_137") (pintype "passive"))
      (node (ref "rxPI1") (pin "138") (pinfunction "GND_138") (pintype "passive"))
      (node (ref "rxPI1") (pin "14") (pinfunction "GND_14") (pintype "passive"))
      (node (ref "rxPI1") (pin "144") (pinfunction "GND_144") (pintype "passive"))
      (node (ref "rxPI1") (pin "150") (pinfunction "GND_150") (pintype "passive"))
      (node (ref "rxPI1") (pin "155") (pinfunction "GND_155") (pintype "passive"))
      (node (ref "rxPI1") (pin "156") (pinfunction "GND_156") (pintype "passive"))
      (node (ref "rxPI1") (pin "161") (pinfunction "GND_161") (pintype "passive"))
      (node (ref "rxPI1") (pin "162") (pinfunction "GND_162") (pintype "passive"))
      (node (ref "rxPI1") (pin "167") (pinfunction "GND_167") (pintype "passive"))
      (node (ref "rxPI1") (pin "168") (pinfunction "GND_168") (pintype "passive"))
      (node (ref "rxPI1") (pin "173") (pinfunction "GND_173") (pintype "passive"))
      (node (ref "rxPI1") (pin "174") (pinfunction "GND_174") (pintype "passive"))
      (node (ref "rxPI1") (pin "179") (pinfunction "GND_179") (pintype "passive"))
      (node (ref "rxPI1") (pin "180") (pinfunction "GND_180") (pintype "passive"))
      (node (ref "rxPI1") (pin "185") (pinfunction "GND_185") (pintype "passive"))
      (node (ref "rxPI1") (pin "186") (pinfunction "GND_186") (pintype "passive"))
      (node (ref "rxPI1") (pin "191") (pinfunction "GND_191") (pintype "passive"))
      (node (ref "rxPI1") (pin "192") (pinfunction "GND_192") (pintype "passive"))
      (node (ref "rxPI1") (pin "197") (pinfunction "GND_197") (pintype "passive"))
      (node (ref "rxPI1") (pin "198") (pinfunction "GND_198") (pintype "passive"))
      (node (ref "rxPI1") (pin "2") (pinfunction "GND_2") (pintype "passive"))
      (node (ref "rxPI1") (pin "201") (pinfunction "GND_201") (pintype "passive"))
      (node (ref "rxPI1") (pin "202") (pinfunction "GND_202") (pintype "passive"))
      (node (ref "rxPI1") (pin "207") (pinfunction "GND_207") (pintype "passive"))
      (node (ref "rxPI1") (pin "213") (pinfunction "GND_213") (pintype "passive"))
      (node (ref "rxPI1") (pin "219") (pinfunction "GND_219") (pintype "passive"))
      (node (ref "rxPI1") (pin "22") (pinfunction "GND_22") (pintype "passive"))
      (node (ref "rxPI1") (pin "222") (pinfunction "GND_222") (pintype "passive"))
      (node (ref "rxPI1") (pin "225") (pinfunction "GND_225") (pintype "passive"))
      (node (ref "rxPI1") (pin "23") (pinfunction "GND_23") (pintype "passive"))
      (node (ref "rxPI1") (pin "231") (pinfunction "GND_231") (pintype "passive"))
      (node (ref "rxPI1") (pin "232") (pinfunction "GND_232") (pintype "passive"))
      (node (ref "rxPI1") (pin "237") (pinfunction "GND_237") (pintype "passive"))
      (node (ref "rxPI1") (pin "242") (pinfunction "GND_242") (pintype "passive"))
      (node (ref "rxPI1") (pin "243") (pinfunction "GND_243") (pintype "passive"))
      (node (ref "rxPI1") (pin "248") (pinfunction "GND_248") (pintype "passive"))
      (node (ref "rxPI1") (pin "249") (pinfunction "GND_249") (pintype "passive"))
      (node (ref "rxPI1") (pin "255") (pinfunction "GND_255") (pintype "passive"))
      (node (ref "rxPI1") (pin "256") (pinfunction "GND_256") (pintype "passive"))
      (node (ref "rxPI1") (pin "261") (pinfunction "GND_261") (pintype "passive"))
      (node (ref "rxPI1") (pin "262") (pinfunction "GND_262") (pintype "passive"))
      (node (ref "rxPI1") (pin "267") (pinfunction "GND_267") (pintype "passive"))
      (node (ref "rxPI1") (pin "268") (pinfunction "GND_268") (pintype "passive"))
      (node (ref "rxPI1") (pin "272") (pinfunction "GND_272") (pintype "passive"))
      (node (ref "rxPI1") (pin "273") (pinfunction "GND_273") (pintype "passive"))
      (node (ref "rxPI1") (pin "276") (pinfunction "GND_276") (pintype "passive"))
      (node (ref "rxPI1") (pin "299") (pinfunction "GND_299") (pintype "passive"))
      (node (ref "rxPI1") (pin "300") (pinfunction "GND_300") (pintype "passive"))
      (node (ref "rxPI1") (pin "32") (pinfunction "GND_32") (pintype "passive"))
      (node (ref "rxPI1") (pin "33") (pinfunction "GND_33") (pintype "passive"))
      (node (ref "rxPI1") (pin "42") (pinfunction "GND_42") (pintype "passive"))
      (node (ref "rxPI1") (pin "43") (pinfunction "GND_43") (pintype "passive"))
      (node (ref "rxPI1") (pin "52") (pinfunction "GND_52") (pintype "passive"))
      (node (ref "rxPI1") (pin "53") (pinfunction "GND_53") (pintype "passive"))
      (node (ref "rxPI1") (pin "60") (pinfunction "GND_60") (pintype "passive"))
      (node (ref "rxPI1") (pin "65") (pinfunction "GND_65") (pintype "passive"))
      (node (ref "rxPI1") (pin "66") (pinfunction "GND_66") (pintype "passive"))
      (node (ref "rxPI1") (pin "7") (pinfunction "GND_7") (pintype "passive"))
      (node (ref "rxPI1") (pin "71") (pinfunction "GND_71") (pintype "passive"))
      (node (ref "rxPI1") (pin "74") (pinfunction "GND_74") (pintype "passive"))
      (node (ref "rxPI1") (pin "8") (pinfunction "GND_8") (pintype "passive"))
      (node (ref "rxPI1") (pin "98") (pinfunction "GND_98") (pintype "passive"))
    )
    (net (code "6") (name "HDMI0_CEC") (class "Default")
      (node (ref "H2") (pin "51") (pinfunction "51_51") (pintype "passive"))
      (node (ref "HB") (pin "52") (pinfunction "52_52") (pintype "passive"))
      (node (ref "rPI1") (pin "151") (pinfunction "HDMI0_CEC_151") (pintype "passive"))
      (node (ref "rxPI1") (pin "151") (pinfunction "HDMI0_CEC_151") (pintype "passive"))
    )
    (net (code "7") (name "HDMI0_CLK_N") (class "Default")
      (node (ref "H2") (pin "90") (pinfunction "90_90") (pintype "passive"))
      (node (ref "HB") (pin "89") (pinfunction "89_89") (pintype "passive"))
      (node (ref "rPI1") (pin "190") (pinfunction "HDMI0_CLK_N_190") (pintype "passive"))
      (node (ref "rxPI1") (pin "190") (pinfunction "HDMI0_CLK_N_190") (pintype "passive"))
    )
    (net (code "8") (name "HDMI0_CLK_P") (class "Default")
      (node (ref "H2") (pin "88") (pinfunction "88_88") (pintype "passive"))
      (node (ref "HB") (pin "87") (pinfunction "87_87") (pintype "passive"))
      (node (ref "rPI1") (pin "188") (pinfunction "HDMI0_CLK_P_188") (pintype "passive"))
      (node (ref "rxPI1") (pin "188") (pinfunction "HDMI0_CLK_P_188") (pintype "passive"))
    )
    (net (code "9") (name "HDMI0_HOTPLUG") (class "Default")
      (node (ref "H2") (pin "53") (pinfunction "53_53") (pintype "passive"))
      (node (ref "HB") (pin "54") (pinfunction "54_54") (pintype "passive"))
      (node (ref "rPI1") (pin "153") (pinfunction "HDMI0_HOTPLUG_153") (pintype "passive"))
      (node (ref "rxPI1") (pin "153") (pinfunction "HDMI0_HOTPLUG_153") (pintype "passive"))
    )
    (net (code "10") (name "HDMI0_SCL") (class "Default")
      (node (ref "H2") (pin "100") (pinfunction "100_100") (pintype "passive"))
      (node (ref "HB") (pin "99") (pinfunction "99_99") (pintype "passive"))
      (node (ref "rPI1") (pin "200") (pinfunction "HDMI0_SCL_200") (pintype "passive"))
      (node (ref "rxPI1") (pin "200") (pinfunction "HDMI0_SCL_200") (pintype "passive"))
    )
    (net (code "11") (name "HDMI0_SDA") (class "Default")
      (node (ref "H2") (pin "99") (pinfunction "99_99") (pintype "passive"))
      (node (ref "HB") (pin "100") (pinfunction "100_100") (pintype "passive"))
      (node (ref "rPI1") (pin "199") (pinfunction "HDMI0_SDA_199") (pintype "passive"))
      (node (ref "rxPI1") (pin "199") (pinfunction "HDMI0_SDA_199") (pintype "passive"))
    )
    (net (code "12") (name "HDMI0_TX0_N") (class "Default")
      (node (ref "H2") (pin "84") (pinfunction "84_84") (pintype "passive"))
      (node (ref "HB") (pin "83") (pinfunction "83_83") (pintype "passive"))
      (node (ref "rPI1") (pin "184") (pinfunction "HDMI0_TX0_N_184") (pintype "passive"))
      (node (ref "rxPI1") (pin "184") (pinfunction "HDMI0_TX0_N_184") (pintype "passive"))
    )
    (net (code "13") (name "HDMI0_TX0_P") (class "Default")
      (node (ref "H2") (pin "82") (pinfunction "82_82") (pintype "passive"))
      (node (ref "HB") (pin "81") (pinfunction "81_81") (pintype "passive"))
      (node (ref "rPI1") (pin "182") (pinfunction "HDMI0_TX0_P_182") (pintype "passive"))
      (node (ref "rxPI1") (pin "182") (pinfunction "HDMI0_TX0_P_182") (pintype "passive"))
    )
    (net (code "14") (name "HDMI0_TX1_N") (class "Default")
      (node (ref "H2") (pin "78") (pinfunction "78_78") (pintype "passive"))
      (node (ref "HB") (pin "77") (pinfunction "77_77") (pintype "passive"))
      (node (ref "rPI1") (pin "178") (pinfunction "HDMI0_TX1_N_178") (pintype "passive"))
      (node (ref "rxPI1") (pin "178") (pinfunction "HDMI0_TX1_N_178") (pintype "passive"))
    )
    (net (code "15") (name "HDMI0_TX1_P") (class "Default")
      (node (ref "H2") (pin "76") (pinfunction "76_76") (pintype "passive"))
      (node (ref "HB") (pin "75") (pinfunction "75_75") (pintype "passive"))
      (node (ref "rPI1") (pin "176") (pinfunction "HDMI0_TX1_P_176") (pintype "passive"))
      (node (ref "rxPI1") (pin "176") (pinfunction "HDMI0_TX1_P_176") (pintype "passive"))
    )
    (net (code "16") (name "HDMI0_TX2_N") (class "Default")
      (node (ref "H2") (pin "72") (pinfunction "72_72") (pintype "passive"))
      (node (ref "HB") (pin "71") (pinfunction "71_71") (pintype "passive"))
      (node (ref "rPI1") (pin "172") (pinfunction "HDMI0_TX2_N_172") (pintype "passive"))
      (node (ref "rxPI1") (pin "172") (pinfunction "HDMI0_TX2_N_172") (pintype "passive"))
    )
    (net (code "17") (name "HDMI0_TX2_P") (class "Default")
      (node (ref "H2") (pin "70") (pinfunction "70_70") (pintype "passive"))
      (node (ref "HB") (pin "69") (pinfunction "69_69") (pintype "passive"))
      (node (ref "rPI1") (pin "170") (pinfunction "HDMI0_TX2_P_170") (pintype "passive"))
      (node (ref "rxPI1") (pin "170") (pinfunction "HDMI0_TX2_P_170") (pintype "passive"))
    )
    (net (code "18") (name "HDMI1_CEC") (class "Default")
      (node (ref "H2") (pin "49") (pinfunction "49_49") (pintype "passive"))
      (node (ref "HB") (pin "50") (pinfunction "50_50") (pintype "passive"))
      (node (ref "rPI1") (pin "149") (pinfunction "HDMI1_CEC_149") (pintype "passive"))
      (node (ref "rxPI1") (pin "149") (pinfunction "HDMI1_CEC_149") (pintype "passive"))
    )
    (net (code "19") (name "HDMI1_CLK_N") (class "Default")
      (node (ref "H2") (pin "66") (pinfunction "66_66") (pintype "passive"))
      (node (ref "HB") (pin "65") (pinfunction "65_65") (pintype "passive"))
      (node (ref "rPI1") (pin "166") (pinfunction "HDMI1_CLK_N_166") (pintype "passive"))
      (node (ref "rxPI1") (pin "166") (pinfunction "HDMI1_CLK_N_166") (pintype "passive"))
    )
    (net (code "20") (name "HDMI1_CLK_P") (class "Default")
      (node (ref "H2") (pin "64") (pinfunction "64_64") (pintype "passive"))
      (node (ref "HB") (pin "63") (pinfunction "63_63") (pintype "passive"))
      (node (ref "rPI1") (pin "164") (pinfunction "HDMI1_CLK_P_164") (pintype "passive"))
      (node (ref "rxPI1") (pin "164") (pinfunction "HDMI1_CLK_P_164") (pintype "passive"))
    )
    (net (code "21") (name "HDMI1_HOTPLUG") (class "Default")
      (node (ref "H2") (pin "43") (pinfunction "43_43") (pintype "passive"))
      (node (ref "HB") (pin "44") (pinfunction "44_44") (pintype "passive"))
      (node (ref "rPI1") (pin "143") (pinfunction "HDMI1_HOTPLUG_143") (pintype "passive"))
      (node (ref "rxPI1") (pin "143") (pinfunction "HDMI1_HOTPLUG_143") (pintype "passive"))
    )
    (net (code "22") (name "HDMI1_SCL") (class "Default")
      (node (ref "H2") (pin "47") (pinfunction "47_47") (pintype "passive"))
      (node (ref "HB") (pin "48") (pinfunction "48_48") (pintype "passive"))
      (node (ref "rPI1") (pin "147") (pinfunction "HDMI1_SCL_147") (pintype "passive"))
      (node (ref "rxPI1") (pin "147") (pinfunction "HDMI1_SCL_147") (pintype "passive"))
    )
    (net (code "23") (name "HDMI1_SDA") (class "Default")
      (node (ref "H2") (pin "45") (pinfunction "45_45") (pintype "passive"))
      (node (ref "HB") (pin "46") (pinfunction "46_46") (pintype "passive"))
      (node (ref "rPI1") (pin "145") (pinfunction "HDMI1_SDA_145") (pintype "passive"))
      (node (ref "rxPI1") (pin "145") (pinfunction "HDMI1_SDA_145") (pintype "passive"))
    )
    (net (code "24") (name "HDMI1_TX0_N") (class "Default")
      (node (ref "H2") (pin "60") (pinfunction "60_60") (pintype "passive"))
      (node (ref "HB") (pin "59") (pinfunction "59_59") (pintype "passive"))
      (node (ref "rPI1") (pin "160") (pinfunction "HDMI1_TX0_N_160") (pintype "passive"))
      (node (ref "rxPI1") (pin "160") (pinfunction "HDMI1_TX0_N_160") (pintype "passive"))
    )
    (net (code "25") (name "HDMI1_TX0_P") (class "Default")
      (node (ref "H2") (pin "58") (pinfunction "58_58") (pintype "passive"))
      (node (ref "HB") (pin "57") (pinfunction "57_57") (pintype "passive"))
      (node (ref "rPI1") (pin "158") (pinfunction "HDMI1_TX0_P_158") (pintype "passive"))
      (node (ref "rxPI1") (pin "158") (pinfunction "HDMI1_TX0_P_158") (pintype "passive"))
    )
    (net (code "26") (name "HDMI1_TX1_N") (class "Default")
      (node (ref "H2") (pin "54") (pinfunction "54_54") (pintype "passive"))
      (node (ref "HB") (pin "53") (pinfunction "53_53") (pintype "passive"))
      (node (ref "rPI1") (pin "154") (pinfunction "HDMI1_TX1_N_154") (pintype "passive"))
      (node (ref "rxPI1") (pin "154") (pinfunction "HDMI1_TX1_N_154") (pintype "passive"))
    )
    (net (code "27") (name "HDMI1_TX1_P") (class "Default")
      (node (ref "H2") (pin "52") (pinfunction "52_52") (pintype "passive"))
      (node (ref "HB") (pin "51") (pinfunction "51_51") (pintype "passive"))
      (node (ref "rPI1") (pin "152") (pinfunction "HDMI1_TX1_P_152") (pintype "passive"))
      (node (ref "rxPI1") (pin "152") (pinfunction "HDMI1_TX1_P_152") (pintype "passive"))
    )
    (net (code "28") (name "HDMI1_TX2_N") (class "Default")
      (node (ref "H2") (pin "48") (pinfunction "48_48") (pintype "passive"))
      (node (ref "HB") (pin "47") (pinfunction "47_47") (pintype "passive"))
      (node (ref "rPI1") (pin "148") (pinfunction "HDMI1_TX2_N_148") (pintype "passive"))
      (node (ref "rxPI1") (pin "148") (pinfunction "HDMI1_TX2_N_148") (pintype "passive"))
    )
    (net (code "29") (name "HDMI1_TX2_P") (class "Default")
      (node (ref "H2") (pin "46") (pinfunction "46_46") (pintype "passive"))
      (node (ref "HB") (pin "45") (pinfunction "45_45") (pintype "passive"))
      (node (ref "rPI1") (pin "146") (pinfunction "HDMI1_TX2_P_146") (pintype "passive"))
      (node (ref "rxPI1") (pin "146") (pinfunction "HDMI1_TX2_P_146") (pintype "passive"))
    )
    (net (code "30") (name "I2C_SCL") (class "Default")
      (node (ref "J3") (pin "72") (pinfunction "72_72") (pintype "passive"))
      (node (ref "U1") (pin "6") (pinfunction "SCL_6") (pintype "input"))
      (node (ref "rxPI1") (pin "271") (pinfunction "I2C6_SCL_M3_271") (pintype "passive"))
    )
    (net (code "31") (name "I2C_SDA") (class "Default")
      (node (ref "J3") (pin "70") (pinfunction "70_70") (pintype "passive"))
      (node (ref "U1") (pin "7") (pinfunction "SDA_7") (pintype "bidirectional"))
      (node (ref "rxPI1") (pin "269") (pinfunction "I2C6_SDA_M3_269") (pintype "passive"))
    )
    (net (code "32") (name "Net-(D1-I{slash}O1-Pad1)") (class "Default")
      (node (ref "D1") (pin "1") (pinfunction "I/O1_1") (pintype "bidirectional"))
      (node (ref "L1") (pin "4") (pinfunction "4_4") (pintype "passive"))
    )
    (net (code "33") (name "Net-(D1-I{slash}O2-Pad3)") (class "Default")
      (node (ref "D1") (pin "3") (pinfunction "I/O2_3") (pintype "bidirectional"))
      (node (ref "L1") (pin "3") (pinfunction "3_3") (pintype "passive"))
    )
    (net (code "34") (name "Net-(H1-Pad59)") (class "Default")
      (node (ref "H1") (pin "59") (pinfunction "59_59") (pintype "passive"))
      (node (ref "HA") (pin "60") (pinfunction "60_60") (pintype "passive"))
      (node (ref "rPI1") (pin "59") (pinfunction "GND_59") (pintype "passive"))
      (node (ref "rxPI1") (pin "59") (pinfunction "GND_59") (pintype "passive"))
    )
    (net (code "35") (name "Net-(H1-Pad86)") (class "Default")
      (node (ref "H1") (pin "86") (pinfunction "86_86") (pintype "passive"))
      (node (ref "HA") (pin "85") (pinfunction "85_85") (pintype "passive"))
      (node (ref "rPI1") (pin "86") (pinfunction "+3.3v_(Output)_86") (pintype "passive"))
      (node (ref "rxPI1") (pin "86") (pinfunction "+3.3v_(Output)_86") (pintype "passive"))
    )
    (net (code "36") (name "Net-(H1-Pad88)") (class "Default")
      (node (ref "H1") (pin "88") (pinfunction "88_88") (pintype "passive"))
      (node (ref "HA") (pin "87") (pinfunction "87_87") (pintype "passive"))
      (node (ref "rPI1") (pin "88") (pinfunction "+1.8v_(Output)_88") (pintype "passive"))
      (node (ref "rxPI1") (pin "88") (pinfunction "+1.8v_(Output)_88") (pintype "passive"))
    )
    (net (code "37") (name "Net-(H1-Pad90)") (class "Default")
      (node (ref "H1") (pin "90") (pinfunction "90_90") (pintype "passive"))
      (node (ref "HA") (pin "89") (pinfunction "89_89") (pintype "passive"))
      (node (ref "rPI1") (pin "90") (pinfunction "+1.8v_(Output)_90") (pintype "passive"))
      (node (ref "rxPI1") (pin "90") (pinfunction "+1.8v_(Output)_90") (pintype "passive"))
    )
    (net (code "38") (name "Net-(J3-Pad15)") (class "Default")
      (node (ref "J3") (pin "15") (pinfunction "15_15") (pintype "passive"))
      (node (ref "rxPI1") (pin "216") (pinfunction "nc_216") (pintype "passive"))
    )
    (net (code "39") (name "Net-(J3-Pad34)") (class "Default")
      (node (ref "J3") (pin "34") (pinfunction "34_34") (pintype "passive"))
      (node (ref "rxPI1") (pin "233") (pinfunction "nc_233") (pintype "passive"))
    )
    (net (code "40") (name "Net-(J3-Pad36)") (class "Default")
      (node (ref "J3") (pin "36") (pinfunction "36_36") (pintype "passive"))
      (node (ref "rxPI1") (pin "235") (pinfunction "nc_235") (pintype "passive"))
    )
    (net (code "41") (name "Net-(J3-Pad49)") (class "Default")
      (node (ref "J3") (pin "49") (pinfunction "49_49") (pintype "passive"))
      (node (ref "rxPI1") (pin "250") (pinfunction "nc_250") (pintype "passive"))
    )
    (net (code "42") (name "Net-(J3-Pad51)") (class "Default")
      (node (ref "J3") (pin "51") (pinfunction "51_51") (pintype "passive"))
      (node (ref "rxPI1") (pin "252") (pinfunction "nc_252") (pintype "passive"))
    )
    (net (code "43") (name "Net-(J3-Pad53)") (class "Default")
      (node (ref "J3") (pin "53") (pinfunction "53_53") (pintype "passive"))
      (node (ref "rxPI1") (pin "254") (pinfunction "nc_254") (pintype "passive"))
    )
    (net (code "44") (name "Net-(J3-Pad57)") (class "Default")
      (node (ref "J3") (pin "57") (pinfunction "57_57") (pintype "passive"))
      (node (ref "rxPI1") (pin "258") (pinfunction "nc_258") (pintype "passive"))
    )
    (net (code "45") (name "Net-(J3-Pad59)") (class "Default")
      (node (ref "J3") (pin "59") (pinfunction "59_59") (pintype "passive"))
      (node (ref "rxPI1") (pin "260") (pinfunction "nc_260") (pintype "passive"))
    )
    (net (code "46") (name "Net-(J3-Pad63)") (class "Default")
      (node (ref "J3") (pin "63") (pinfunction "63_63") (pintype "passive"))
      (node (ref "rxPI1") (pin "264") (pinfunction "nc_264") (pintype "passive"))
    )
    (net (code "47") (name "Net-(J3-Pad65)") (class "Default")
      (node (ref "J3") (pin "65") (pinfunction "65_65") (pintype "passive"))
      (node (ref "rxPI1") (pin "266") (pinfunction "nc_266") (pintype "passive"))
    )
    (net (code "48") (name "Net-(J3-Pad69)") (class "Default")
      (node (ref "J3") (pin "69") (pinfunction "69_69") (pintype "passive"))
      (node (ref "rxPI1") (pin "270") (pinfunction "nc_270") (pintype "passive"))
    )
    (net (code "49") (name "Net-(J3-Pad77)") (class "Default")
      (node (ref "J3") (pin "77") (pinfunction "77_77") (pintype "passive"))
      (node (ref "rxPI1") (pin "278") (pinfunction "nc_278") (pintype "passive"))
    )
    (net (code "50") (name "Net-(J3-Pad79)") (class "Default")
      (node (ref "J3") (pin "79") (pinfunction "79_79") (pintype "passive"))
      (node (ref "rxPI1") (pin "280") (pinfunction "nc_280") (pintype "passive"))
    )
    (net (code "51") (name "Net-(J3-Pad81)") (class "Default")
      (node (ref "J3") (pin "81") (pinfunction "81_81") (pintype "passive"))
      (node (ref "rxPI1") (pin "282") (pinfunction "nc_282") (pintype "passive"))
    )
    (net (code "52") (name "Net-(J3-Pad83)") (class "Default")
      (node (ref "J3") (pin "83") (pinfunction "83_83") (pintype "passive"))
      (node (ref "rxPI1") (pin "284") (pinfunction "nc_284") (pintype "passive"))
    )
    (net (code "53") (name "Net-(J3-Pad85)") (class "Default")
      (node (ref "J3") (pin "85") (pinfunction "85_85") (pintype "passive"))
      (node (ref "rxPI1") (pin "286") (pinfunction "nc_286") (pintype "passive"))
    )
    (net (code "54") (name "Net-(J3-Pad87)") (class "Default")
      (node (ref "J3") (pin "87") (pinfunction "87_87") (pintype "passive"))
      (node (ref "rxPI1") (pin "288") (pinfunction "nc_288") (pintype "passive"))
    )
    (net (code "55") (name "Net-(J3-Pad89)") (class "Default")
      (node (ref "J3") (pin "89") (pinfunction "89_89") (pintype "passive"))
      (node (ref "rxPI1") (pin "290") (pinfunction "nc_290") (pintype "passive"))
    )
    (net (code "56") (name "Net-(J3-Pad92)") (class "Default")
      (node (ref "J3") (pin "92") (pinfunction "92_92") (pintype "passive"))
      (node (ref "rxPI1") (pin "291") (pinfunction "nc_291") (pintype "passive"))
    )
    (net (code "57") (name "Net-(L2-VIN)") (class "Default")
      (node (ref "FB1") (pin "1") (pinfunction "1_1") (pintype "passive"))
      (node (ref "L2") (pin "3") (pinfunction "VIN_3") (pintype "power_in"))
    )
    (net (code "58") (name "Net-(L2-VOUT)") (class "Default")
      (node (ref "L2") (pin "2") (pinfunction "VOUT_2") (pintype "power_in"))
      (node (ref "L3") (pin "1") (pinfunction "1_1") (pintype "passive"))
    )
    (net (code "59") (name "Net-(L4-VIN)") (class "Default")
      (node (ref "FB2") (pin "1") (pinfunction "1_1") (pintype "passive"))
      (node (ref "L4") (pin "3") (pinfunction "VIN_3") (pintype "power_in"))
    )
    (net (code "60") (name "Net-(L4-VOUT)") (class "Default")
      (node (ref "L4") (pin "2") (pinfunction "VOUT_2") (pintype "power_in"))
      (node (ref "L5") (pin "1") (pinfunction "1_1") (pintype "passive"))
    )
    (net (code "61") (name "Net-(U2-GANGED{slash}SMBA2{slash}HS_UP)") (class "Default")
      (node (ref "R7") (pin "2") (pinfunction "2_2") (pintype "passive"))
      (node (ref "U2") (pin "35") (pinfunction "GANGED/SMBA2/HS_UP_35") (pintype "input"))
    )
    (net (code "62") (name "Net-(U2-GRSTZ)") (class "Default")
      (node (ref "C1") (pin "2") (pinfunction "2_2") (pintype "passive"))
      (node (ref "U2") (pin "11") (pinfunction "GRSTZ_11") (pintype "input"))
    )
    (net (code "63") (name "Net-(U2-PWRCRL_POL{slash}SS_DN1)") (class "Default")
      (node (ref "R6") (pin "2") (pinfunction "2_2") (pintype "passive"))
      (node (ref "U2") (pin "21") (pinfunction "PWRCRL_POL/SS_DN1_21") (pintype "bidirectional"))
    )
    (net (code "64") (name "Net-(U2-TEST)") (class "Default")
      (node (ref "R8") (pin "2") (pinfunction "2_2") (pintype "passive"))
      (node (ref "U2") (pin "10") (pinfunction "TEST_10") (pintype "input"))
    )
    (net (code "65") (name "Net-(U2-USB_R1)") (class "Default")
      (node (ref "R1") (pin "2") (pinfunction "2_2") (pintype "passive"))
      (node (ref "U2") (pin "24") (pinfunction "USB_R1_24") (pintype "input"))
    )
    (net (code "66") (name "Net-(U2-USB_SSTXM_DN1)") (class "Default")
      (node (ref "C21") (pin "2") (pinfunction "2_2") (pintype "passive"))
      (node (ref "U2") (pin "44") (pinfunction "USB_SSTXM_DN1_44") (pintype "output"))
    )
    (net (code "67") (name "Net-(U2-USB_SSTXM_DN2)") (class "Default")
      (node (ref "C23") (pin "2") (pinfunction "2_2") (pintype "passive"))
      (node (ref "U2") (pin "17") (pinfunction "USB_SSTXM_DN2_17") (pintype "output"))
    )
    (net (code "68") (name "Net-(U2-USB_SSTXM_UP)") (class "Default")
      (node (ref "C19") (pin "2") (pinfunction "2_2") (pintype "passive"))
      (node (ref "U2") (pin "28") (pinfunction "USB_SSTXM_UP_28") (pintype "output"))
    )
    (net (code "69") (name "Net-(U2-USB_SSTXP_DN1)") (class "Default")
      (node (ref "C20") (pin "2") (pinfunction "2_2") (pintype "passive"))
      (node (ref "U2") (pin "43") (pinfunction "USB_SSTXP_DN1_43") (pintype "output"))
    )
    (net (code "70") (name "Net-(U2-USB_SSTXP_DN2)") (class "Default")
      (node (ref "C22") (pin "2") (pinfunction "2_2") (pintype "passive"))
      (node (ref "U2") (pin "16") (pinfunction "USB_SSTXP_DN2_16") (pintype "output"))
    )
    (net (code "71") (name "Net-(U2-USB_SSTXP_UP)") (class "Default")
      (node (ref "C18") (pin "2") (pinfunction "2_2") (pintype "passive"))
      (node (ref "U2") (pin "29") (pinfunction "USB_SSTXP_UP_29") (pintype "output"))
    )
    (net (code "72") (name "Net-(U2-USB_VBUS)") (class "Default")
      (node (ref "R4") (pin "2") (pinfunction "2_2") (pintype "passive"))
      (node (ref "R5") (pin "2") (pinfunction "2_2") (pintype "passive"))
      (node (ref "U2") (pin "9") (pinfunction "USB_VBUS_9") (pintype "input"))
    )
    (net (code "73") (name "Net-(U2-XI)") (class "Default")
      (node (ref "C24") (pin "2") (pinfunction "2_2") (pintype "passive"))
      (node (ref "R9") (pin "1") (pinfunction "1_1") (pintype "passive"))
      (node (ref "U2") (pin "38") (pinfunction "XI_38") (pintype "input"))
      (node (ref "Y1") (pin "3") (pintype "passive"))
    )
    (net (code "74") (name "Net-(U2-XO)") (class "Default")
      (node (ref "C25") (pin "2") (pinfunction "2_2") (pintype "passive"))
      (node (ref "R9") (pin "2") (pinfunction "2_2") (pintype "passive"))
      (node (ref "U2") (pin "39") (pinfunction "XO_39") (pintype "output"))
      (node (ref "Y1") (pin "1") (pintype "passive"))
    )
    (net (code "75") (name "Net-(rPI1A-BT_nDisable)") (class "Default")
      (node (ref "H1") (pin "91") (pinfunction "91_91") (pintype "passive"))
      (node (ref "HA") (pin "92") (pinfunction "92_92") (pintype "passive"))
      (node (ref "rPI1") (pin "91") (pinfunction "BT_nDisable_91") (pintype "passive"))
      (node (ref "rxPI1") (pin "91") (pinfunction "BT_nDisable_91") (pintype "passive"))
    )
    (net (code "76") (name "Net-(rPI1A-CAM_GPIO1)") (class "Default")
      (node (ref "H1") (pin "100") (pinfunction "100_100") (pintype "passive"))
      (node (ref "HA") (pin "99") (pinfunction "99_99") (pintype "passive"))
      (node (ref "rPI1") (pin "100") (pinfunction "CAM_GPIO1_100") (pintype "passive"))
      (node (ref "rxPI1") (pin "100") (pinfunction "nEXTRST_100") (pintype "passive"))
    )
    (net (code "77") (name "Net-(rPI1A-CC1)") (class "Default")
      (node (ref "H1") (pin "94") (pinfunction "94_94") (pintype "passive"))
      (node (ref "HA") (pin "93") (pinfunction "93_93") (pintype "passive"))
      (node (ref "rPI1") (pin "94") (pinfunction "CC1_94") (pintype "passive"))
      (node (ref "rxPI1") (pin "94") (pinfunction "AnalogIP0_94") (pintype "passive"))
    )
    (net (code "78") (name "Net-(rPI1A-CC2)") (class "Default")
      (node (ref "H1") (pin "96") (pinfunction "96_96") (pintype "passive"))
      (node (ref "HA") (pin "95") (pinfunction "95_95") (pintype "passive"))
      (node (ref "rPI1") (pin "96") (pinfunction "CC2_96") (pintype "passive"))
      (node (ref "rxPI1") (pin "96") (pinfunction "AnalogIP1_96") (pintype "passive"))
    )
    (net (code "79") (name "Net-(rPI1A-Camera_GPIO)") (class "Default")
      (node (ref "H1") (pin "97") (pinfunction "97_97") (pintype "passive"))
      (node (ref "HA") (pin "98") (pinfunction "98_98") (pintype "passive"))
      (node (ref "rPI1") (pin "97") (pinfunction "Camera_GPIO_97") (pintype "passive"))
      (node (ref "rxPI1") (pin "97") (pinfunction "Camera_GPIO_97") (pintype "passive"))
    )
    (net (code "80") (name "Net-(rPI1A-EEPROM_nWP)") (class "Default")
      (node (ref "H1") (pin "20") (pinfunction "20_20") (pintype "passive"))
      (node (ref "HA") (pin "19") (pinfunction "19_19") (pintype "passive"))
      (node (ref "rPI1") (pin "20") (pinfunction "EEPROM_nWP_20") (pintype "passive"))
      (node (ref "rxPI1") (pin "20") (pinfunction "EEPROM_nWP_20") (pintype "passive"))
    )
    (net (code "81") (name "Net-(rPI1A-Ethernet_Pair0_N)") (class "Default")
      (node (ref "H1") (pin "10") (pinfunction "10_10") (pintype "passive"))
      (node (ref "HA") (pin "9") (pinfunction "9_9") (pintype "passive"))
      (node (ref "rPI1") (pin "10") (pinfunction "Ethernet_Pair0_N_10") (pintype "passive"))
      (node (ref "rxPI1") (pin "10") (pinfunction "Ethernet_Pair0_N_10") (pintype "passive"))
    )
    (net (code "82") (name "Net-(rPI1A-Ethernet_Pair0_P)") (class "Default")
      (node (ref "H1") (pin "12") (pinfunction "12_12") (pintype "passive"))
      (node (ref "HA") (pin "11") (pinfunction "11_11") (pintype "passive"))
      (node (ref "rPI1") (pin "12") (pinfunction "Ethernet_Pair0_P_12") (pintype "passive"))
      (node (ref "rxPI1") (pin "12") (pinfunction "Ethernet_Pair0_P_12") (pintype "passive"))
    )
    (net (code "83") (name "Net-(rPI1A-Ethernet_Pair1_N)") (class "Default")
      (node (ref "H1") (pin "6") (pinfunction "6_6") (pintype "passive"))
      (node (ref "HA") (pin "5") (pinfunction "5_5") (pintype "passive"))
      (node (ref "rPI1") (pin "6") (pinfunction "Ethernet_Pair1_N_6") (pintype "passive"))
      (node (ref "rxPI1") (pin "6") (pinfunction "Ethernet_Pair1_N_6") (pintype "passive"))
    )
    (net (code "84") (name "Net-(rPI1A-Ethernet_Pair1_P)") (class "Default")
      (node (ref "H1") (pin "4") (pinfunction "4_4") (pintype "passive"))
      (node (ref "HA") (pin "3") (pinfunction "3_3") (pintype "passive"))
      (node (ref "rPI1") (pin "4") (pinfunction "Ethernet_Pair1_P_4") (pintype "passive"))
      (node (ref "rxPI1") (pin "4") (pinfunction "Ethernet_Pair1_P_4") (pintype "passive"))
    )
    (net (code "85") (name "Net-(rPI1A-Ethernet_Pair2_N)") (class "Default")
      (node (ref "H1") (pin "9") (pinfunction "9_9") (pintype "passive"))
      (node (ref "HA") (pin "10") (pinfunction "10_10") (pintype "passive"))
      (node (ref "rPI1") (pin "9") (pinfunction "Ethernet_Pair2_N_9") (pintype "passive"))
      (node (ref "rxPI1") (pin "9") (pinfunction "Ethernet_Pair2_N_9") (pintype "passive"))
    )
    (net (code "86") (name "Net-(rPI1A-Ethernet_Pair2_P)") (class "Default")
      (node (ref "H1") (pin "11") (pinfunction "11_11") (pintype "passive"))
      (node (ref "HA") (pin "12") (pinfunction "12_12") (pintype "passive"))
      (node (ref "rPI1") (pin "11") (pinfunction "Ethernet_Pair2_P_11") (pintype "passive"))
      (node (ref "rxPI1") (pin "11") (pinfunction "Ethernet_Pair2_P_11") (pintype "passive"))
    )
    (net (code "87") (name "Net-(rPI1A-Ethernet_Pair3_N)") (class "Default")
      (node (ref "H1") (pin "5") (pinfunction "5_5") (pintype "passive"))
      (node (ref "HA") (pin "6") (pinfunction "6_6") (pintype "passive"))
      (node (ref "rPI1") (pin "5") (pinfunction "Ethernet_Pair3_N_5") (pintype "passive"))
      (node (ref "rxPI1") (pin "5") (pinfunction "Ethernet_Pair3_N_5") (pintype "passive"))
    )
    (net (code "88") (name "Net-(rPI1A-Ethernet_Pair3_P)") (class "Default")
      (node (ref "H1") (pin "3") (pinfunction "3_3") (pintype "passive"))
      (node (ref "HA") (pin "4") (pinfunction "4_4") (pintype "passive"))
      (node (ref "rPI1") (pin "3") (pinfunction "Ethernet_Pair3_P_3") (pintype "passive"))
      (node (ref "rxPI1") (pin "3") (pinfunction "Ethernet_Pair3_P_3") (pintype "passive"))
    )
    (net (code "89") (name "Net-(rPI1A-Ethernet_SYNC_IN(1.8v))") (class "Default")
      (node (ref "H1") (pin "16") (pinfunction "16_16") (pintype "passive"))
      (node (ref "HA") (pin "15") (pinfunction "15_15") (pintype "passive"))
      (node (ref "rPI1") (pin "16") (pinfunction "Ethernet_SYNC_IN(1.8v)_16") (pintype "passive"))
      (node (ref "rxPI1") (pin "16") (pinfunction "Ethernet_SYNC_IN(1.8v)_16") (pintype "passive"))
    )
    (net (code "90") (name "Net-(rPI1A-Ethernet_SYNC_OUT(1.8v))") (class "Default")
      (node (ref "H1") (pin "18") (pinfunction "18_18") (pintype "passive"))
      (node (ref "HA") (pin "17") (pinfunction "17_17") (pintype "passive"))
      (node (ref "rPI1") (pin "18") (pinfunction "Ethernet_SYNC_OUT(1.8v)_18") (pintype "passive"))
      (node (ref "rxPI1") (pin "18") (pinfunction "Ethernet_SYNC_OUT(1.8v)_18") (pintype "passive"))
    )
    (net (code "91") (name "Net-(rPI1A-Ethernet_nLED2(3.3v))") (class "Default")
      (node (ref "H1") (pin "17") (pinfunction "17_17") (pintype "passive"))
      (node (ref "HA") (pin "18") (pinfunction "18_18") (pintype "passive"))
      (node (ref "rPI1") (pin "17") (pinfunction "Ethernet_nLED2(3.3v)_17") (pintype "passive"))
      (node (ref "rxPI1") (pin "17") (pinfunction "Ethernet_nLED2(3.3v)_17") (pintype "passive"))
    )
    (net (code "92") (name "Net-(rPI1A-Ethernet_nLED3(3.3v))") (class "Default")
      (node (ref "H1") (pin "15") (pinfunction "15_15") (pintype "passive"))
      (node (ref "HA") (pin "16") (pinfunction "16_16") (pintype "passive"))
      (node (ref "rPI1") (pin "15") (pinfunction "Ethernet_nLED3(3.3v)_15") (pintype "passive"))
      (node (ref "rxPI1") (pin "15") (pinfunction "Ethernet_nLED3(3.3v)_15") (pintype "passive"))
    )
    (net (code "93") (name "Net-(rPI1A-FAN_PWM)") (class "Default")
      (node (ref "H1") (pin "19") (pinfunction "19_19") (pintype "passive"))
      (node (ref "HA") (pin "20") (pinfunction "20_20") (pintype "passive"))
      (node (ref "rPI1") (pin "19") (pinfunction "FAN_PWM_19") (pintype "passive"))
      (node (ref "rxPI1") (pin "19") (pinfunction "Ethernet_nLED1(3.3v)_19") (pintype "passive"))
    )
    (net (code "94") (name "Net-(rPI1A-GPIO2)") (class "Default")
      (node (ref "H1") (pin "58") (pinfunction "58_58") (pintype "passive"))
      (node (ref "HA") (pin "57") (pinfunction "57_57") (pintype "passive"))
      (node (ref "rPI1") (pin "58") (pinfunction "GPIO2_58") (pintype "passive"))
      (node (ref "rxPI1") (pin "58") (pinfunction "GPIO2_58") (pintype "passive"))
    )
    (net (code "95") (name "Net-(rPI1A-GPIO3)") (class "Default")
      (node (ref "H1") (pin "56") (pinfunction "56_56") (pintype "passive"))
      (node (ref "HA") (pin "55") (pinfunction "55_55") (pintype "passive"))
      (node (ref "rPI1") (pin "56") (pinfunction "GPIO3_56") (pintype "passive"))
      (node (ref "rxPI1") (pin "56") (pinfunction "GPIO3_56") (pintype "passive"))
    )
    (net (code "96") (name "Net-(rPI1A-GPIO4)") (class "Default")
      (node (ref "H1") (pin "54") (pinfunction "54_54") (pintype "passive"))
      (node (ref "HA") (pin "53") (pinfunction "53_53") (pintype "passive"))
      (node (ref "rPI1") (pin "54") (pinfunction "GPIO4_54") (pintype "passive"))
      (node (ref "rxPI1") (pin "54") (pinfunction "GPIO4_54") (pintype "passive"))
    )
    (net (code "97") (name "Net-(rPI1A-GPIO5)") (class "Default")
      (node (ref "H1") (pin "34") (pinfunction "34_34") (pintype "passive"))
      (node (ref "HA") (pin "33") (pinfunction "33_33") (pintype "passive"))
      (node (ref "rPI1") (pin "34") (pinfunction "GPIO5_34") (pintype "passive"))
      (node (ref "rxPI1") (pin "34") (pinfunction "GPIO5_34") (pintype "passive"))
    )
    (net (code "98") (name "Net-(rPI1A-GPIO6)") (class "Default")
      (node (ref "H1") (pin "30") (pinfunction "30_30") (pintype "passive"))
      (node (ref "HA") (pin "29") (pinfunction "29_29") (pintype "passive"))
      (node (ref "rPI1") (pin "30") (pinfunction "GPIO6_30") (pintype "passive"))
      (node (ref "rxPI1") (pin "30") (pinfunction "GPIO6_30") (pintype "passive"))
    )
    (net (code "99") (name "Net-(rPI1A-GPIO7)") (class "Default")
      (node (ref "H1") (pin "37") (pinfunction "37_37") (pintype "passive"))
      (node (ref "HA") (pin "38") (pinfunction "38_38") (pintype "passive"))
      (node (ref "rPI1") (pin "37") (pinfunction "GPIO7_37") (pintype "passive"))
      (node (ref "rxPI1") (pin "37") (pinfunction "GPIO7_37") (pintype "passive"))
    )
    (net (code "100") (name "Net-(rPI1A-GPIO8)") (class "Default")
      (node (ref "H1") (pin "39") (pinfunction "39_39") (pintype "passive"))
      (node (ref "HA") (pin "40") (pinfunction "40_40") (pintype "passive"))
      (node (ref "rPI1") (pin "39") (pinfunction "GPIO8_39") (pintype "passive"))
      (node (ref "rxPI1") (pin "39") (pinfunction "GPIO8_39") (pintype "passive"))
    )
    (net (code "101") (name "Net-(rPI1A-GPIO9)") (class "Default")
      (node (ref "H1") (pin "40") (pinfunction "40_40") (pintype "passive"))
      (node (ref "HA") (pin "39") (pinfunction "39_39") (pintype "passive"))
      (node (ref "rPI1") (pin "40") (pinfunction "GPIO9_40") (pintype "passive"))
      (node (ref "rxPI1") (pin "40") (pinfunction "GPIO9_40") (pintype "passive"))
    )
    (net (code "102") (name "Net-(rPI1A-GPIO10)") (class "Default")
      (node (ref "H1") (pin "44") (pinfunction "44_44") (pintype "passive"))
      (node (ref "HA") (pin "43") (pinfunction "43_43") (pintype "passive"))
      (node (ref "rPI1") (pin "44") (pinfunction "GPIO10_44") (pintype "passive"))
      (node (ref "rxPI1") (pin "44") (pinfunction "GPIO10_44") (pintype "passive"))
    )
    (net (code "103") (name "Net-(rPI1A-GPIO11)") (class "Default")
      (node (ref "H1") (pin "38") (pinfunction "38_38") (pintype "passive"))
      (node (ref "HA") (pin "37") (pinfunction "37_37") (pintype "passive"))
      (node (ref "rPI1") (pin "38") (pinfunction "GPIO11_38") (pintype "passive"))
      (node (ref "rxPI1") (pin "38") (pinfunction "GPIO11_38") (pintype "passive"))
    )
    (net (code "104") (name "Net-(rPI1A-GPIO12)") (class "Default")
      (node (ref "H1") (pin "31") (pinfunction "31_31") (pintype "passive"))
      (node (ref "HA") (pin "32") (pinfunction "32_32") (pintype "passive"))
      (node (ref "rPI1") (pin "31") (pinfunction "GPIO12_31") (pintype "passive"))
      (node (ref "rxPI1") (pin "31") (pinfunction "GPIO12_31") (pintype "passive"))
    )
    (net (code "105") (name "Net-(rPI1A-GPIO13)") (class "Default")
      (node (ref "H1") (pin "28") (pinfunction "28_28") (pintype "passive"))
      (node (ref "HA") (pin "27") (pinfunction "27_27") (pintype "passive"))
      (node (ref "rPI1") (pin "28") (pinfunction "GPIO13_28") (pintype "passive"))
      (node (ref "rxPI1") (pin "28") (pinfunction "GPIO13_28") (pintype "passive"))
    )
    (net (code "106") (name "Net-(rPI1A-GPIO14)") (class "Default")
      (node (ref "H1") (pin "55") (pinfunction "55_55") (pintype "passive"))
      (node (ref "HA") (pin "56") (pinfunction "56_56") (pintype "passive"))
      (node (ref "rPI1") (pin "55") (pinfunction "GPIO14_55") (pintype "passive"))
      (node (ref "rxPI1") (pin "55") (pinfunction "GPIO14_55") (pintype "passive"))
    )
    (net (code "107") (name "Net-(rPI1A-GPIO15)") (class "Default")
      (node (ref "H1") (pin "51") (pinfunction "51_51") (pintype "passive"))
      (node (ref "HA") (pin "52") (pinfunction "52_52") (pintype "passive"))
      (node (ref "rPI1") (pin "51") (pinfunction "GPIO15_51") (pintype "passive"))
      (node (ref "rxPI1") (pin "51") (pinfunction "GPIO15_51") (pintype "passive"))
    )
    (net (code "108") (name "Net-(rPI1A-GPIO16)") (class "Default")
      (node (ref "H1") (pin "29") (pinfunction "29_29") (pintype "passive"))
      (node (ref "HA") (pin "30") (pinfunction "30_30") (pintype "passive"))
      (node (ref "rPI1") (pin "29") (pinfunction "GPIO16_29") (pintype "passive"))
      (node (ref "rxPI1") (pin "29") (pinfunction "GPIO16_29") (pintype "passive"))
    )
    (net (code "109") (name "Net-(rPI1A-GPIO17)") (class "Default")
      (node (ref "H1") (pin "50") (pinfunction "50_50") (pintype "passive"))
      (node (ref "HA") (pin "49") (pinfunction "49_49") (pintype "passive"))
      (node (ref "rPI1") (pin "50") (pinfunction "GPIO17_50") (pintype "passive"))
      (node (ref "rxPI1") (pin "50") (pinfunction "GPIO17_50") (pintype "passive"))
    )
    (net (code "110") (name "Net-(rPI1A-GPIO18)") (class "Default")
      (node (ref "H1") (pin "49") (pinfunction "49_49") (pintype "passive"))
      (node (ref "HA") (pin "50") (pinfunction "50_50") (pintype "passive"))
      (node (ref "rPI1") (pin "49") (pinfunction "GPIO18_49") (pintype "passive"))
      (node (ref "rxPI1") (pin "49") (pinfunction "GPIO18_49") (pintype "passive"))
    )
    (net (code "111") (name "Net-(rPI1A-GPIO19)") (class "Default")
      (node (ref "H1") (pin "26") (pinfunction "26_26") (pintype "passive"))
      (node (ref "HA") (pin "25") (pinfunction "25_25") (pintype "passive"))
      (node (ref "rPI1") (pin "26") (pinfunction "GPIO19_26") (pintype "passive"))
      (node (ref "rxPI1") (pin "26") (pinfunction "GPIO19_26") (pintype "passive"))
    )
    (net (code "112") (name "Net-(rPI1A-GPIO20)") (class "Default")
      (node (ref "H1") (pin "27") (pinfunction "27_27") (pintype "passive"))
      (node (ref "HA") (pin "28") (pinfunction "28_28") (pintype "passive"))
      (node (ref "rPI1") (pin "27") (pinfunction "GPIO20_27") (pintype "passive"))
      (node (ref "rxPI1") (pin "27") (pinfunction "GPIO20_27") (pintype "passive"))
    )
    (net (code "113") (name "Net-(rPI1A-GPIO21)") (class "Default")
      (node (ref "H1") (pin "25") (pinfunction "25_25") (pintype "passive"))
      (node (ref "HA") (pin "26") (pinfunction "26_26") (pintype "passive"))
      (node (ref "rPI1") (pin "25") (pinfunction "GPIO21_25") (pintype "passive"))
      (node (ref "rxPI1") (pin "25") (pinfunction "GPIO21_25") (pintype "passive"))
    )
    (net (code "114") (name "Net-(rPI1A-GPIO22)") (class "Default")
      (node (ref "H1") (pin "46") (pinfunction "46_46") (pintype "passive"))
      (node (ref "HA") (pin "45") (pinfunction "45_45") (pintype "passive"))
      (node (ref "rPI1") (pin "46") (pinfunction "GPIO22_46") (pintype "passive"))
      (node (ref "rxPI1") (pin "46") (pinfunction "GPIO22_46") (pintype "passive"))
    )
    (net (code "115") (name "Net-(rPI1A-GPIO23)") (class "Default")
      (node (ref "H1") (pin "47") (pinfunction "47_47") (pintype "passive"))
      (node (ref "HA") (pin "48") (pinfunction "48_48") (pintype "passive"))
      (node (ref "rPI1") (pin "47") (pinfunction "GPIO23_47") (pintype "passive"))
      (node (ref "rxPI1") (pin "47") (pinfunction "GPIO23_47") (pintype "passive"))
    )
    (net (code "116") (name "Net-(rPI1A-GPIO24)") (class "Default")
      (node (ref "H1") (pin "45") (pinfunction "45_45") (pintype "passive"))
      (node (ref "HA") (pin "46") (pinfunction "46_46") (pintype "passive"))
      (node (ref "rPI1") (pin "45") (pinfunction "GPIO24_45") (pintype "passive"))
      (node (ref "rxPI1") (pin "45") (pinfunction "GPIO24_45") (pintype "passive"))
    )
    (net (code "117") (name "Net-(rPI1A-GPIO25)") (class "Default")
      (node (ref "H1") (pin "41") (pinfunction "41_41") (pintype "passive"))
      (node (ref "HA") (pin "42") (pinfunction "42_42") (pintype "passive"))
      (node (ref "rPI1") (pin "41") (pinfunction "GPIO25_41") (pintype "passive"))
      (node (ref "rxPI1") (pin "41") (pinfunction "GPIO25_41") (pintype "passive"))
    )
    (net (code "118") (name "Net-(rPI1A-GPIO26)") (class "Default")
      (node (ref "H1") (pin "24") (pinfunction "24_24") (pintype "passive"))
      (node (ref "HA") (pin "23") (pinfunction "23_23") (pintype "passive"))
      (node (ref "rPI1") (pin "24") (pinfunction "GPIO26_24") (pintype "passive"))
      (node (ref "rxPI1") (pin "24") (pinfunction "GPIO26_24") (pintype "passive"))
    )
    (net (code "119") (name "Net-(rPI1A-GPIO27)") (class "Default")
      (node (ref "H1") (pin "48") (pinfunction "48_48") (pintype "passive"))
      (node (ref "HA") (pin "47") (pinfunction "47_47") (pintype "passive"))
      (node (ref "rPI1") (pin "48") (pinfunction "GPIO27_48") (pintype "passive"))
      (node (ref "rxPI1") (pin "48") (pinfunction "GPIO27_48") (pintype "passive"))
    )
    (net (code "120") (name "Net-(rPI1A-GPIO_VREF(1.8v{slash}3.3v_Input))") (class "Default")
      (node (ref "H1") (pin "78") (pinfunction "78_78") (pintype "passive"))
      (node (ref "HA") (pin "77") (pinfunction "77_77") (pintype "passive"))
      (node (ref "rPI1") (pin "78") (pinfunction "GPIO_VREF(1.8v/3.3v_Input)_78") (pintype "passive"))
      (node (ref "rxPI1") (pin "78") (pinfunction "GPIO_VREF(1.8v/3.3v_Input)_78") (pintype "passive"))
    )
    (net (code "121") (name "Net-(rPI1A-Global_EN)") (class "Default")
      (node (ref "H1") (pin "99") (pinfunction "99_99") (pintype "passive"))
      (node (ref "HA") (pin "100") (pinfunction "100_100") (pintype "passive"))
      (node (ref "rPI1") (pin "99") (pinfunction "Global_EN_99") (pintype "passive"))
      (node (ref "rxPI1") (pin "99") (pinfunction "Global_EN_99") (pintype "passive"))
    )
    (net (code "122") (name "Net-(rPI1A-ID_SC)") (class "Default")
      (node (ref "H1") (pin "35") (pinfunction "35_35") (pintype "passive"))
      (node (ref "HA") (pin "36") (pinfunction "36_36") (pintype "passive"))
      (node (ref "rPI1") (pin "35") (pinfunction "ID_SC_35") (pintype "passive"))
      (node (ref "rxPI1") (pin "35") (pinfunction "ID_SC_35") (pintype "passive"))
    )
    (net (code "123") (name "Net-(rPI1A-ID_SD)") (class "Default")
      (node (ref "H1") (pin "36") (pinfunction "36_36") (pintype "passive"))
      (node (ref "HA") (pin "35") (pinfunction "35_35") (pintype "passive"))
      (node (ref "rPI1") (pin "36") (pinfunction "ID_SD_36") (pintype "passive"))
      (node (ref "rxPI1") (pin "36") (pinfunction "ID_SD_36") (pintype "passive"))
    )
    (net (code "124") (name "Net-(rPI1A-PI_nLED_Activity)") (class "Default")
      (node (ref "H1") (pin "21") (pinfunction "21_21") (pintype "passive"))
      (node (ref "HA") (pin "22") (pinfunction "22_22") (pintype "passive"))
      (node (ref "rPI1") (pin "21") (pinfunction "PI_nLED_Activity_21") (pintype "passive"))
      (node (ref "rxPI1") (pin "21") (pinfunction "PI_nLED_Activity_21") (pintype "passive"))
    )
    (net (code "125") (name "Net-(rPI1A-RUN_PG)") (class "Default")
      (node (ref "H1") (pin "92") (pinfunction "92_92") (pintype "passive"))
      (node (ref "HA") (pin "91") (pinfunction "91_91") (pintype "passive"))
      (node (ref "rPI1") (pin "92") (pinfunction "RUN_PG_92") (pintype "passive"))
      (node (ref "rxPI1") (pin "92") (pinfunction "RUN_PG_92") (pintype "passive"))
    )
    (net (code "126") (name "Net-(rPI1A-Reserved)") (class "Default")
      (node (ref "H1") (pin "76") (pinfunction "76_76") (pintype "passive"))
      (node (ref "HA") (pin "75") (pinfunction "75_75") (pintype "passive"))
      (node (ref "rPI1") (pin "76") (pinfunction "Reserved_76") (pintype "passive"))
      (node (ref "rxPI1") (pin "76") (pinfunction "Reserved_76") (pintype "passive"))
    )
    (net (code "127") (name "Net-(rPI1A-SCL0)") (class "Default")
      (node (ref "H1") (pin "80") (pinfunction "80_80") (pintype "passive"))
      (node (ref "HA") (pin "79") (pinfunction "79_79") (pintype "passive"))
      (node (ref "rPI1") (pin "80") (pinfunction "SCL0_80") (pintype "passive"))
      (node (ref "rxPI1") (pin "80") (pinfunction "SCL0_80") (pintype "passive"))
    )
    (net (code "128") (name "Net-(rPI1A-SDA0)") (class "Default")
      (node (ref "H1") (pin "82") (pinfunction "82_82") (pintype "passive"))
      (node (ref "HA") (pin "81") (pinfunction "81_81") (pintype "passive"))
      (node (ref "rPI1") (pin "82") (pinfunction "SDA0_82") (pintype "passive"))
      (node (ref "rxPI1") (pin "82") (pinfunction "SDA0_82") (pintype "passive"))
    )
    (net (code "129") (name "Net-(rPI1A-SD_CLK)") (class "Default")
      (node (ref "H1") (pin "57") (pinfunction "57_57") (pintype "passive"))
      (node (ref "HA") (pin "58") (pinfunction "58_58") (pintype "passive"))
      (node (ref "rPI1") (pin "57") (pinfunction "SD_CLK_57") (pintype "passive"))
      (node (ref "rxPI1") (pin "57") (pinfunction "SD_CLK_57") (pintype "passive"))
    )
    (net (code "130") (name "Net-(rPI1A-SD_CMD)") (class "Default")
      (node (ref "H1") (pin "62") (pinfunction "62_62") (pintype "passive"))
      (node (ref "HA") (pin "61") (pinfunction "61_61") (pintype "passive"))
      (node (ref "rPI1") (pin "62") (pinfunction "SD_CMD_62") (pintype "passive"))
      (node (ref "rxPI1") (pin "62") (pinfunction "SD_CMD_62") (pintype "passive"))
    )
    (net (code "131") (name "Net-(rPI1A-SD_DAT0)") (class "Default")
      (node (ref "H1") (pin "63") (pinfunction "63_63") (pintype "passive"))
      (node (ref "HA") (pin "64") (pinfunction "64_64") (pintype "passive"))
      (node (ref "rPI1") (pin "63") (pinfunction "SD_DAT0_63") (pintype "passive"))
      (node (ref "rxPI1") (pin "63") (pinfunction "SD_DAT0_63") (pintype "passive"))
    )
    (net (code "132") (name "Net-(rPI1A-SD_DAT1)") (class "Default")
      (node (ref "H1") (pin "67") (pinfunction "67_67") (pintype "passive"))
      (node (ref "HA") (pin "68") (pinfunction "68_68") (pintype "passive"))
      (node (ref "rPI1") (pin "67") (pinfunction "SD_DAT1_67") (pintype "passive"))
      (node (ref "rxPI1") (pin "67") (pinfunction "SD_DAT1_67") (pintype "passive"))
    )
    (net (code "133") (name "Net-(rPI1A-SD_DAT2)") (class "Default")
      (node (ref "H1") (pin "69") (pinfunction "69_69") (pintype "passive"))
      (node (ref "HA") (pin "70") (pinfunction "70_70") (pintype "passive"))
      (node (ref "rPI1") (pin "69") (pinfunction "SD_DAT2_69") (pintype "passive"))
      (node (ref "rxPI1") (pin "69") (pinfunction "SD_DAT2_69") (pintype "passive"))
    )
    (net (code "134") (name "Net-(rPI1A-SD_DAT3)") (class "Default")
      (node (ref "H1") (pin "61") (pinfunction "61_61") (pintype "passive"))
      (node (ref "HA") (pin "62") (pinfunction "62_62") (pintype "passive"))
      (node (ref "rPI1") (pin "61") (pinfunction "SD_DAT3_61") (pintype "passive"))
      (node (ref "rxPI1") (pin "61") (pinfunction "SD_DAT3_61") (pintype "passive"))
    )
    (net (code "135") (name "Net-(rPI1A-SD_DAT4)") (class "Default")
      (node (ref "H1") (pin "68") (pinfunction "68_68") (pintype "passive"))
      (node (ref "HA") (pin "67") (pinfunction "67_67") (pintype "passive"))
      (node (ref "rPI1") (pin "68") (pinfunction "SD_DAT4_68") (pintype "passive"))
      (node (ref "rxPI1") (pin "68") (pinfunction "SD_DAT4_68") (pintype "passive"))
    )
    (net (code "136") (name "Net-(rPI1A-SD_DAT5)") (class "Default")
      (node (ref "H1") (pin "64") (pinfunction "64_64") (pintype "passive"))
      (node (ref "HA") (pin "63") (pinfunction "63_63") (pintype "passive"))
      (node (ref "rPI1") (pin "64") (pinfunction "SD_DAT5_64") (pintype "passive"))
      (node (ref "rxPI1") (pin "64") (pinfunction "SD_DAT5_64") (pintype "passive"))
    )
    (net (code "137") (name "Net-(rPI1A-SD_DAT6)") (class "Default")
      (node (ref "H1") (pin "72") (pinfunction "72_72") (pintype "passive"))
      (node (ref "HA") (pin "71") (pinfunction "71_71") (pintype "passive"))
      (node (ref "rPI1") (pin "72") (pinfunction "SD_DAT6_72") (pintype "passive"))
      (node (ref "rxPI1") (pin "72") (pinfunction "SD_DAT6_72") (pintype "passive"))
    )
    (net (code "138") (name "Net-(rPI1A-SD_DAT7)") (class "Default")
      (node (ref "H1") (pin "70") (pinfunction "70_70") (pintype "passive"))
      (node (ref "HA") (pin "69") (pinfunction "69_69") (pintype "passive"))
      (node (ref "rPI1") (pin "70") (pinfunction "SD_DAT7_70") (pintype "passive"))
      (node (ref "rxPI1") (pin "70") (pinfunction "SD_DAT7_70") (pintype "passive"))
    )
    (net (code "139") (name "Net-(rPI1A-SD_PWR_ON)") (class "Default")
      (node (ref "H1") (pin "75") (pinfunction "75_75") (pintype "passive"))
      (node (ref "HA") (pin "76") (pinfunction "76_76") (pintype "passive"))
      (node (ref "rPI1") (pin "75") (pinfunction "SD_PWR_ON_75") (pintype "passive"))
      (node (ref "rxPI1") (pin "75") (pinfunction "SD_PWR_ON_75") (pintype "passive"))
    )
    (net (code "140") (name "Net-(rPI1A-SD_VDD_Override)") (class "Default")
      (node (ref "H1") (pin "73") (pinfunction "73_73") (pintype "passive"))
      (node (ref "HA") (pin "74") (pinfunction "74_74") (pintype "passive"))
      (node (ref "rPI1") (pin "73") (pinfunction "SD_VDD_Override_73") (pintype "passive"))
      (node (ref "rxPI1") (pin "73") (pinfunction "SD_VDD_Override_73") (pintype "passive"))
    )
    (net (code "141") (name "Net-(rPI1A-WiFi_nDisable)") (class "Default")
      (node (ref "H1") (pin "89") (pinfunction "89_89") (pintype "passive"))
      (node (ref "HA") (pin "90") (pinfunction "90_90") (pintype "passive"))
      (node (ref "rPI1") (pin "89") (pinfunction "WiFi_nDisable_89") (pintype "passive"))
      (node (ref "rxPI1") (pin "89") (pinfunction "WiFi_nDisable_89") (pintype "passive"))
    )
    (net (code "142") (name "Net-(rPI1A-nPI_LED_PWR)") (class "Default")
      (node (ref "H1") (pin "95") (pinfunction "95_95") (pintype "passive"))
      (node (ref "HA") (pin "96") (pinfunction "96_96") (pintype "passive"))
      (node (ref "rPI1") (pin "95") (pinfunction "nPI_LED_PWR_95") (pintype "passive"))
      (node (ref "rxPI1") (pin "95") (pinfunction "nPI_LED_PWR_95") (pintype "passive"))
    )
    (net (code "143") (name "Net-(rPI1A-nRPIBOOT)") (class "Default")
      (node (ref "H1") (pin "93") (pinfunction "93_93") (pintype "passive"))
      (node (ref "HA") (pin "94") (pinfunction "94_94") (pintype "passive"))
      (node (ref "rPI1") (pin "93") (pinfunction "nRPIBOOT_93") (pintype "passive"))
      (node (ref "rxPI1") (pin "93") (pinfunction "nRPIBOOT_93") (pintype "passive"))
    )
    (net (code "144") (name "Net-(rPI1B-MIPI0_C_N)") (class "Default")
      (node (ref "HB") (pin "28") (pinfunction "28_28") (pintype "passive"))
      (node (ref "rPI1") (pin "127") (pinfunction "MIPI0_C_N_127") (pintype "passive"))
    )
    (net (code "145") (name "Net-(rPI1B-MIPI0_C_P)") (class "Default")
      (node (ref "HB") (pin "30") (pinfunction "30_30") (pintype "passive"))
      (node (ref "rPI1") (pin "129") (pinfunction "MIPI0_C_P_129") (pintype "passive"))
    )
    (net (code "146") (name "Net-(rPI1B-MIPI0_D0_N)") (class "Default")
      (node (ref "HB") (pin "16") (pinfunction "16_16") (pintype "passive"))
      (node (ref "rPI1") (pin "115") (pinfunction "MIPI0_D0_N_115") (pintype "passive"))
    )
    (net (code "147") (name "Net-(rPI1B-MIPI0_D0_P)") (class "Default")
      (node (ref "HB") (pin "18") (pinfunction "18_18") (pintype "passive"))
      (node (ref "rPI1") (pin "117") (pinfunction "MIPI0_D0_P_117") (pintype "passive"))
    )
    (net (code "148") (name "Net-(rPI1B-MIPI0_D1_N)") (class "Default")
      (node (ref "HB") (pin "22") (pinfunction "22_22") (pintype "passive"))
      (node (ref "rPI1") (pin "121") (pinfunction "MIPI0_D1_N_121") (pintype "passive"))
    )
    (net (code "149") (name "Net-(rPI1B-MIPI0_D1_P)") (class "Default")
      (node (ref "HB") (pin "24") (pinfunction "24_24") (pintype "passive"))
      (node (ref "rPI1") (pin "123") (pinfunction "MIPI0_D1_P_123") (pintype "passive"))
    )
    (net (code "150") (name "Net-(rPI1B-MIPI0_D2_N)") (class "Default")
      (node (ref "HB") (pin "34") (pinfunction "34_34") (pintype "passive"))
      (node (ref "rPI1") (pin "133") (pinfunction "MIPI0_D2_N_133") (pintype "passive"))
    )
    (net (code "151") (name "Net-(rPI1B-MIPI0_D2_P)") (class "Default")
      (node (ref "HB") (pin "36") (pinfunction "36_36") (pintype "passive"))
      (node (ref "rPI1") (pin "135") (pinfunction "MIPI0_D2_P_135") (pintype "passive"))
    )
    (net (code "152") (name "Net-(rPI1B-MIPI0_D3_N)") (class "Default")
      (node (ref "HB") (pin "40") (pinfunction "40_40") (pintype "passive"))
      (node (ref "rPI1") (pin "139") (pinfunction "MIPI0_D3_N_139") (pintype "passive"))
    )
    (net (code "153") (name "Net-(rPI1B-MIPI0_D3_P)") (class "Default")
      (node (ref "HB") (pin "42") (pinfunction "42_42") (pintype "passive"))
      (node (ref "rPI1") (pin "141") (pinfunction "MIPI0_D3_P_141") (pintype "passive"))
    )
    (net (code "154") (name "Net-(rPI1B-MIPI1_C_N)") (class "Default")
      (node (ref "HB") (pin "88") (pinfunction "88_88") (pintype "passive"))
      (node (ref "rPI1") (pin "187") (pinfunction "MIPI1_C_N_187") (pintype "passive"))
    )
    (net (code "155") (name "Net-(rPI1B-MIPI1_C_P)") (class "Default")
      (node (ref "HB") (pin "90") (pinfunction "90_90") (pintype "passive"))
      (node (ref "rPI1") (pin "189") (pinfunction "MIPI1_C_P_189") (pintype "passive"))
    )
    (net (code "156") (name "Net-(rPI1B-MIPI1_D0_N)") (class "Default")
      (node (ref "HB") (pin "76") (pinfunction "76_76") (pintype "passive"))
      (node (ref "rPI1") (pin "175") (pinfunction "MIPI1_D0_N_175") (pintype "passive"))
    )
    (net (code "157") (name "Net-(rPI1B-MIPI1_D0_P)") (class "Default")
      (node (ref "HB") (pin "78") (pinfunction "78_78") (pintype "passive"))
      (node (ref "rPI1") (pin "177") (pinfunction "MIPI1_D0_P_177") (pintype "passive"))
    )
    (net (code "158") (name "Net-(rPI1B-MIPI1_D1_N)") (class "Default")
      (node (ref "HB") (pin "82") (pinfunction "82_82") (pintype "passive"))
      (node (ref "rPI1") (pin "181") (pinfunction "MIPI1_D1_N_181") (pintype "passive"))
    )
    (net (code "159") (name "Net-(rPI1B-MIPI1_D1_P)") (class "Default")
      (node (ref "HB") (pin "84") (pinfunction "84_84") (pintype "passive"))
      (node (ref "rPI1") (pin "183") (pinfunction "MIPI1_D1_P_183") (pintype "passive"))
    )
    (net (code "160") (name "Net-(rPI1B-MIPI1_D2_N)") (class "Default")
      (node (ref "HB") (pin "94") (pinfunction "94_94") (pintype "passive"))
      (node (ref "rPI1") (pin "193") (pinfunction "MIPI1_D2_N_193") (pintype "passive"))
    )
    (net (code "161") (name "Net-(rPI1B-MIPI1_D2_P)") (class "Default")
      (node (ref "HB") (pin "96") (pinfunction "96_96") (pintype "passive"))
      (node (ref "rPI1") (pin "195") (pinfunction "MIPI1_D2_P_195") (pintype "passive"))
    )
    (net (code "162") (name "Net-(rPI1B-MIPI1_D3_N)") (class "Default")
      (node (ref "HB") (pin "93") (pinfunction "93_93") (pintype "passive"))
      (node (ref "rPI1") (pin "194") (pinfunction "MIPI1_D3_N_194") (pintype "passive"))
    )
    (net (code "163") (name "Net-(rPI1B-MIPI1_D3_P)") (class "Default")
      (node (ref "HB") (pin "95") (pinfunction "95_95") (pintype "passive"))
      (node (ref "rPI1") (pin "196") (pinfunction "MIPI1_D3_P_196") (pintype "passive"))
    )
    (net (code "164") (name "Net-(rPI1B-VBUS_EN)") (class "Default")
      (node (ref "HB") (pin "12") (pinfunction "12_12") (pintype "passive"))
      (node (ref "rPI1") (pin "111") (pinfunction "VBUS_EN_111") (pintype "passive"))
    )
    (net (code "165") (name "Net-(rxPI1B-CAM0_C_N)") (class "Default")
      (node (ref "H2") (pin "40") (pinfunction "40_40") (pintype "passive"))
      (node (ref "rxPI1") (pin "140") (pinfunction "CAM0_C_N_140") (pintype "passive"))
    )
    (net (code "166") (name "Net-(rxPI1B-CAM0_C_P)") (class "Default")
      (node (ref "H2") (pin "42") (pinfunction "42_42") (pintype "passive"))
      (node (ref "rxPI1") (pin "142") (pinfunction "CAM0_C_P_142") (pintype "passive"))
    )
    (net (code "167") (name "Net-(rxPI1B-CAM0_D0_N)") (class "Default")
      (node (ref "H2") (pin "28") (pinfunction "28_28") (pintype "passive"))
      (node (ref "rxPI1") (pin "128") (pinfunction "CAM0_D0_N_128") (pintype "passive"))
    )
    (net (code "168") (name "Net-(rxPI1B-CAM0_D0_P)") (class "Default")
      (node (ref "H2") (pin "30") (pinfunction "30_30") (pintype "passive"))
      (node (ref "rxPI1") (pin "130") (pinfunction "CAM0_D0_P_130") (pintype "passive"))
    )
    (net (code "169") (name "Net-(rxPI1B-CAM0_D1_N)") (class "Default")
      (node (ref "H2") (pin "34") (pinfunction "34_34") (pintype "passive"))
      (node (ref "rxPI1") (pin "134") (pinfunction "CAM0_D1_N_134") (pintype "passive"))
    )
    (net (code "170") (name "Net-(rxPI1B-CAM0_D1_P)") (class "Default")
      (node (ref "H2") (pin "36") (pinfunction "36_36") (pintype "passive"))
      (node (ref "rxPI1") (pin "136") (pinfunction "CAM0_D1_P_136") (pintype "passive"))
    )
    (net (code "171") (name "Net-(rxPI1B-CAM1_C_N)") (class "Default")
      (node (ref "H2") (pin "27") (pinfunction "27_27") (pintype "passive"))
      (node (ref "rxPI1") (pin "127") (pinfunction "CAM1_C_N_127") (pintype "passive"))
    )
    (net (code "172") (name "Net-(rxPI1B-CAM1_C_P)") (class "Default")
      (node (ref "H2") (pin "29") (pinfunction "29_29") (pintype "passive"))
      (node (ref "rxPI1") (pin "129") (pinfunction "CAM1_C_P_129") (pintype "passive"))
    )
    (net (code "173") (name "Net-(rxPI1B-CAM1_D0_N)") (class "Default")
      (node (ref "H2") (pin "15") (pinfunction "15_15") (pintype "passive"))
      (node (ref "rxPI1") (pin "115") (pinfunction "CAM1_D0_N_115") (pintype "passive"))
    )
    (net (code "174") (name "Net-(rxPI1B-CAM1_D0_P)") (class "Default")
      (node (ref "H2") (pin "17") (pinfunction "17_17") (pintype "passive"))
      (node (ref "rxPI1") (pin "117") (pinfunction "CAM1_D0_P_117") (pintype "passive"))
    )
    (net (code "175") (name "Net-(rxPI1B-CAM1_D1_N)") (class "Default")
      (node (ref "H2") (pin "21") (pinfunction "21_21") (pintype "passive"))
      (node (ref "rxPI1") (pin "121") (pinfunction "CAM1_D1_N_121") (pintype "passive"))
    )
    (net (code "176") (name "Net-(rxPI1B-CAM1_D1_P)") (class "Default")
      (node (ref "H2") (pin "23") (pinfunction "23_23") (pintype "passive"))
      (node (ref "rxPI1") (pin "123") (pinfunction "CAM1_D1_P_123") (pintype "passive"))
    )
    (net (code "177") (name "Net-(rxPI1B-CAM1_D2_N)") (class "Default")
      (node (ref "H2") (pin "33") (pinfunction "33_33") (pintype "passive"))
      (node (ref "rxPI1") (pin "133") (pinfunction "CAM1_D2_N_133") (pintype "passive"))
    )
    (net (code "178") (name "Net-(rxPI1B-CAM1_D2_P)") (class "Default")
      (node (ref "H2") (pin "35") (pinfunction "35_35") (pintype "passive"))
      (node (ref "rxPI1") (pin "135") (pinfunction "CAM1_D2_P_135") (pintype "passive"))
    )
    (net (code "179") (name "Net-(rxPI1B-CAM1_D3_N)") (class "Default")
      (node (ref "H2") (pin "39") (pinfunction "39_39") (pintype "passive"))
      (node (ref "rxPI1") (pin "139") (pinfunction "CAM1_D3_N_139") (pintype "passive"))
    )
    (net (code "180") (name "Net-(rxPI1B-CAM1_D3_P)") (class "Default")
      (node (ref "H2") (pin "41") (pinfunction "41_41") (pintype "passive"))
      (node (ref "rxPI1") (pin "141") (pinfunction "CAM1_D3_P_141") (pintype "passive"))
    )
    (net (code "181") (name "Net-(rxPI1B-DSI0_C_N)") (class "Default")
      (node (ref "H2") (pin "69") (pinfunction "69_69") (pintype "passive"))
      (node (ref "rxPI1") (pin "169") (pinfunction "DSI0_C_N_169") (pintype "passive"))
    )
    (net (code "182") (name "Net-(rxPI1B-DSI0_C_P)") (class "Default")
      (node (ref "H2") (pin "71") (pinfunction "71_71") (pintype "passive"))
      (node (ref "rxPI1") (pin "171") (pinfunction "DSI0_C_P_171") (pintype "passive"))
    )
    (net (code "183") (name "Net-(rxPI1B-DSI0_D0_N)") (class "Default")
      (node (ref "H2") (pin "57") (pinfunction "57_57") (pintype "passive"))
      (node (ref "rxPI1") (pin "157") (pinfunction "DSI0_D0_N_157") (pintype "passive"))
    )
    (net (code "184") (name "Net-(rxPI1B-DSI0_D0_P)") (class "Default")
      (node (ref "H2") (pin "59") (pinfunction "59_59") (pintype "passive"))
      (node (ref "rxPI1") (pin "159") (pinfunction "DSI0_D0_P_159") (pintype "passive"))
    )
    (net (code "185") (name "Net-(rxPI1B-DSI0_D1_N)") (class "Default")
      (node (ref "H2") (pin "63") (pinfunction "63_63") (pintype "passive"))
      (node (ref "rxPI1") (pin "163") (pinfunction "DSI0_D1_N_163") (pintype "passive"))
    )
    (net (code "186") (name "Net-(rxPI1B-DSI0_D1_P)") (class "Default")
      (node (ref "H2") (pin "65") (pinfunction "65_65") (pintype "passive"))
      (node (ref "rxPI1") (pin "165") (pinfunction "DSI0_D1_P_165") (pintype "passive"))
    )
    (net (code "187") (name "Net-(rxPI1B-DSI1_C_N)") (class "Default")
      (node (ref "H2") (pin "87") (pinfunction "87_87") (pintype "passive"))
      (node (ref "rxPI1") (pin "187") (pinfunction "DSI1_C_N_187") (pintype "passive"))
    )
    (net (code "188") (name "Net-(rxPI1B-DSI1_C_P)") (class "Default")
      (node (ref "H2") (pin "89") (pinfunction "89_89") (pintype "passive"))
      (node (ref "rxPI1") (pin "189") (pinfunction "DSI1_C_P_189") (pintype "passive"))
    )
    (net (code "189") (name "Net-(rxPI1B-DSI1_D0_N)") (class "Default")
      (node (ref "H2") (pin "75") (pinfunction "75_75") (pintype "passive"))
      (node (ref "rxPI1") (pin "175") (pinfunction "DSI1_D0_N_175") (pintype "passive"))
    )
    (net (code "190") (name "Net-(rxPI1B-DSI1_D0_P)") (class "Default")
      (node (ref "H2") (pin "77") (pinfunction "77_77") (pintype "passive"))
      (node (ref "rxPI1") (pin "177") (pinfunction "DSI1_D0_P_177") (pintype "passive"))
    )
    (net (code "191") (name "Net-(rxPI1B-DSI1_D1_N)") (class "Default")
      (node (ref "H2") (pin "81") (pinfunction "81_81") (pintype "passive"))
      (node (ref "rxPI1") (pin "181") (pinfunction "DSI1_D1_N_181") (pintype "passive"))
    )
    (net (code "192") (name "Net-(rxPI1B-DSI1_D1_P)") (class "Default")
      (node (ref "H2") (pin "83") (pinfunction "83_83") (pintype "passive"))
      (node (ref "rxPI1") (pin "183") (pinfunction "DSI1_D1_P_183") (pintype "passive"))
    )
    (net (code "193") (name "Net-(rxPI1B-DSI1_D2_N)") (class "Default")
      (node (ref "H2") (pin "93") (pinfunction "93_93") (pintype "passive"))
      (node (ref "rxPI1") (pin "193") (pinfunction "DSI1_D2_N_193") (pintype "passive"))
    )
    (net (code "194") (name "Net-(rxPI1B-DSI1_D2_P)") (class "Default")
      (node (ref "H2") (pin "95") (pinfunction "95_95") (pintype "passive"))
      (node (ref "rxPI1") (pin "195") (pinfunction "DSI1_D2_P_195") (pintype "passive"))
    )
    (net (code "195") (name "Net-(rxPI1B-DSI1_D3_N)") (class "Default")
      (node (ref "H2") (pin "94") (pinfunction "94_94") (pintype "passive"))
      (node (ref "rxPI1") (pin "194") (pinfunction "DSI1_D3_N_194") (pintype "passive"))
    )
    (net (code "196") (name "Net-(rxPI1B-DSI1_D3_P)") (class "Default")
      (node (ref "H2") (pin "96") (pinfunction "96_96") (pintype "passive"))
      (node (ref "rxPI1") (pin "196") (pinfunction "DSI1_D3_P_196") (pintype "passive"))
    )
    (net (code "197") (name "Net-(rxPI1B-VDAC_COMP)") (class "Default")
      (node (ref "H2") (pin "11") (pinfunction "11_11") (pintype "passive"))
      (node (ref "rxPI1") (pin "111") (pinfunction "VDAC_COMP_111") (pintype "passive"))
    )
    (net (code "198") (name "Net-(rxPI1C-BT_HOST_WAKE)") (class "Default")
      (node (ref "J3") (pin "86") (pinfunction "86_86") (pintype "passive"))
      (node (ref "rxPI1") (pin "285") (pinfunction "BT_HOST_WAKE_285") (pintype "passive"))
    )
    (net (code "199") (name "Net-(rxPI1C-BT_REG_ON_H)") (class "Default")
      (node (ref "J3") (pin "97") (pinfunction "97_97") (pintype "passive"))
      (node (ref "rxPI1") (pin "298") (pinfunction "BT_REG_ON_H_298") (pintype "passive"))
    )
    (net (code "200") (name "Net-(rxPI1C-GPIO0_C2)") (class "Default")
      (node (ref "J3") (pin "94") (pinfunction "94_94") (pintype "passive"))
      (node (ref "rxPI1") (pin "293") (pinfunction "GPIO0_C2_293") (pintype "passive"))
    )
    (net (code "201") (name "Net-(rxPI1C-GPIO0_D3)") (class "Default")
      (node (ref "J3") (pin "93") (pinfunction "93_93") (pintype "passive"))
      (node (ref "rxPI1") (pin "294") (pinfunction "GPIO0_D3_294") (pintype "passive"))
    )
    (net (code "202") (name "Net-(rxPI1C-GPIO1_B6_CAM2_CLK)") (class "Default")
      (node (ref "J3") (pin "9") (pinfunction "9_9") (pintype "passive"))
      (node (ref "rxPI1") (pin "210") (pinfunction "GPIO1_B6_CAM2_CLK_210") (pintype "passive"))
    )
    (net (code "203") (name "Net-(rxPI1C-GPIO1_B7)") (class "Default")
      (node (ref "J3") (pin "11") (pinfunction "11_11") (pintype "passive"))
      (node (ref "rxPI1") (pin "212") (pinfunction "GPIO1_B7_212") (pintype "passive"))
    )
    (net (code "204") (name "Net-(rxPI1C-GPIO1_C1)") (class "Default")
      (node (ref "J3") (pin "19") (pinfunction "19_19") (pintype "passive"))
      (node (ref "rxPI1") (pin "220") (pinfunction "GPIO1_C1_220") (pintype "passive"))
    )
    (net (code "205") (name "Net-(rxPI1C-GPIO1_C4_S)") (class "Default")
      (node (ref "J3") (pin "80") (pinfunction "80_80") (pintype "passive"))
      (node (ref "rxPI1") (pin "279") (pinfunction "GPIO1_C4_S_279") (pintype "passive"))
    )
    (net (code "206") (name "Net-(rxPI1C-GPIO1_C6_S)") (class "Default")
      (node (ref "J3") (pin "76") (pinfunction "76_76") (pintype "passive"))
      (node (ref "rxPI1") (pin "275") (pinfunction "GPIO1_C6_S_275") (pintype "passive"))
    )
    (net (code "207") (name "Net-(rxPI1C-GPIO1_D0)") (class "Default")
      (node (ref "J3") (pin "43") (pinfunction "43_43") (pintype "passive"))
      (node (ref "rxPI1") (pin "244") (pinfunction "GPIO1_D0_244") (pintype "passive"))
    )
    (net (code "208") (name "Net-(rxPI1C-GPIO1_D1)") (class "Default")
      (node (ref "J3") (pin "45") (pinfunction "45_45") (pintype "passive"))
      (node (ref "rxPI1") (pin "246") (pinfunction "GPIO1_D1_246") (pintype "passive"))
    )
    (net (code "209") (name "Net-(rxPI1C-GPIO1_D2)") (class "Default")
      (node (ref "J3") (pin "84") (pinfunction "84_84") (pintype "passive"))
      (node (ref "rxPI1") (pin "283") (pinfunction "GPIO1_D2_283") (pintype "passive"))
    )
    (net (code "210") (name "Net-(rxPI1C-GPIO1_D5_S)") (class "Default")
      (node (ref "J3") (pin "78") (pinfunction "78_78") (pintype "passive"))
      (node (ref "rxPI1") (pin "277") (pinfunction "GPIO1_D5_S_277") (pintype "passive"))
    )
    (net (code "211") (name "Net-(rxPI1C-GPIO3_B7)") (class "Default")
      (node (ref "J3") (pin "5") (pinfunction "5_5") (pintype "passive"))
      (node (ref "rxPI1") (pin "206") (pinfunction "GPIO3_B7_206") (pintype "passive"))
    )
    (net (code "212") (name "Net-(rxPI1C-GPIO3_C0)") (class "Default")
      (node (ref "J3") (pin "3") (pinfunction "3_3") (pintype "passive"))
      (node (ref "rxPI1") (pin "204") (pinfunction "GPIO3_C0_204") (pintype "passive"))
    )
    (net (code "213") (name "Net-(rxPI1C-GPIO4_A4)") (class "Default")
      (node (ref "J3") (pin "37") (pinfunction "37_37") (pintype "passive"))
      (node (ref "rxPI1") (pin "238") (pinfunction "GPIO4_A4_238") (pintype "passive"))
    )
    (net (code "214") (name "Net-(rxPI1C-GPIO4_A5)") (class "Default")
      (node (ref "J3") (pin "39") (pinfunction "39_39") (pintype "passive"))
      (node (ref "rxPI1") (pin "240") (pinfunction "GPIO4_A5_240") (pintype "passive"))
    )
    (net (code "215") (name "Net-(rxPI1C-GPIO4_A6)") (class "Default")
      (node (ref "J3") (pin "90") (pinfunction "90_90") (pintype "passive"))
      (node (ref "rxPI1") (pin "289") (pinfunction "GPIO4_A6_289") (pintype "passive"))
    )
    (net (code "216") (name "Net-(rxPI1C-GPIO4_A7)") (class "Default")
      (node (ref "J3") (pin "88") (pinfunction "88_88") (pintype "passive"))
      (node (ref "rxPI1") (pin "287") (pinfunction "GPIO4_A7_287") (pintype "passive"))
    )
    (net (code "217") (name "Net-(rxPI1C-HP_DET_L)") (class "Default")
      (node (ref "J3") (pin "35") (pinfunction "35_35") (pintype "passive"))
      (node (ref "rxPI1") (pin "236") (pinfunction "HP_DET_L_236") (pintype "passive"))
    )
    (net (code "218") (name "Net-(rxPI1C-LCD_PWREN_H)") (class "Default")
      (node (ref "J3") (pin "33") (pinfunction "33_33") (pintype "passive"))
      (node (ref "rxPI1") (pin "234") (pinfunction "LCD_PWREN_H_234") (pintype "passive"))
    )
    (net (code "219") (name "Net-(rxPI1C-PCIE20_2_REFCLKN)") (class "Default")
      (node (ref "J3") (pin "42") (pinfunction "42_42") (pintype "passive"))
      (node (ref "rxPI1") (pin "241") (pinfunction "PCIE20_2_REFCLKN_241") (pintype "passive"))
    )
    (net (code "220") (name "Net-(rxPI1C-PCIE20_2_REFCLKP)") (class "Default")
      (node (ref "J3") (pin "40") (pinfunction "40_40") (pintype "passive"))
      (node (ref "rxPI1") (pin "239") (pinfunction "PCIE20_2_REFCLKP_239") (pintype "passive"))
    )
    (net (code "221") (name "Net-(rxPI1C-PWM11_M3)") (class "Default")
      (node (ref "J3") (pin "17") (pinfunction "17_17") (pintype "passive"))
      (node (ref "rxPI1") (pin "218") (pinfunction "PWM11_M3_218") (pintype "passive"))
    )
    (net (code "222") (name "Net-(rxPI1C-RTC_INT_L)") (class "Default")
      (node (ref "J3") (pin "82") (pinfunction "82_82") (pintype "passive"))
      (node (ref "rxPI1") (pin "281") (pinfunction "RTC_INT_L_281") (pintype "passive"))
    )
    (net (code "223") (name "Net-(rxPI1C-SARADC_VIN0_KEY{slash}RECOVERY)") (class "Default")
      (node (ref "J3") (pin "25") (pinfunction "25_25") (pintype "passive"))
      (node (ref "rxPI1") (pin "226") (pinfunction "SARADC_VIN0_KEY/RECOVERY_226") (pintype "passive"))
    )
    (net (code "224") (name "Net-(rxPI1C-SARADC_VIN1_DC)") (class "Default")
      (node (ref "J3") (pin "27") (pinfunction "27_27") (pintype "passive"))
      (node (ref "rxPI1") (pin "228") (pinfunction "SARADC_VIN1_DC_228") (pintype "passive"))
    )
    (net (code "225") (name "Net-(rxPI1C-SARADC_VIN2_HP_HOOK)") (class "Default")
      (node (ref "J3") (pin "29") (pinfunction "29_29") (pintype "passive"))
      (node (ref "rxPI1") (pin "230") (pinfunction "SARADC_VIN2_HP_HOOK_230") (pintype "passive"))
    )
    (net (code "226") (name "Net-(rxPI1C-SDMMC_DET_L)") (class "Default")
      (node (ref "J3") (pin "73") (pinfunction "73_73") (pintype "passive"))
      (node (ref "rxPI1") (pin "274") (pinfunction "SDMMC_DET_L_274") (pintype "passive"))
    )
    (net (code "227") (name "Net-(rxPI1C-TYPEC0_OTG_VBUSDET)") (class "Default")
      (node (ref "J3") (pin "98") (pinfunction "98_98") (pintype "passive"))
      (node (ref "rxPI1") (pin "297") (pinfunction "TYPEC0_OTG_VBUSDET_297") (pintype "passive"))
    )
    (net (code "228") (name "Net-(rxPI1C-TYPEC0_SBU1)") (class "Default")
      (node (ref "J3") (pin "4") (pinfunction "4_4") (pintype "passive"))
      (node (ref "rxPI1") (pin "203") (pinfunction "TYPEC0_SBU1_203") (pintype "passive"))
    )
    (net (code "229") (name "Net-(rxPI1C-TYPEC0_SBU1_DC)") (class "Default")
      (node (ref "J3") (pin "7") (pinfunction "7_7") (pintype "passive"))
      (node (ref "rxPI1") (pin "208") (pinfunction "TYPEC0_SBU1_DC_208") (pintype "passive"))
    )
    (net (code "230") (name "Net-(rxPI1C-TYPEC0_SBU2)") (class "Default")
      (node (ref "J3") (pin "6") (pinfunction "6_6") (pintype "passive"))
      (node (ref "rxPI1") (pin "205") (pinfunction "TYPEC0_SBU2_205") (pintype "passive"))
    )
    (net (code "231") (name "Net-(rxPI1C-TYPEC0_SBU2_DC)") (class "Default")
      (node (ref "J3") (pin "13") (pinfunction "13_13") (pintype "passive"))
      (node (ref "rxPI1") (pin "214") (pinfunction "TYPEC0_SBU2_DC_214") (pintype "passive"))
    )
    (net (code "232") (name "Net-(rxPI1C-TYPEC0_SSRX1N)") (class "Default")
      (node (ref "J3") (pin "12") (pinfunction "12_12") (pintype "passive"))
      (node (ref "rxPI1") (pin "211") (pinfunction "TYPEC0_SSRX1N_211") (pintype "passive"))
    )
    (net (code "233") (name "Net-(rxPI1C-TYPEC0_SSRX1P)") (class "Default")
      (node (ref "J3") (pin "10") (pinfunction "10_10") (pintype "passive"))
      (node (ref "rxPI1") (pin "209") (pinfunction "TYPEC0_SSRX1P_209") (pintype "passive"))
    )
    (net (code "234") (name "Net-(rxPI1C-TYPEC0_SSRX2N)") (class "Default")
      (node (ref "J3") (pin "24") (pinfunction "24_24") (pintype "passive"))
      (node (ref "rxPI1") (pin "223") (pinfunction "TYPEC0_SSRX2N_223") (pintype "passive"))
    )
    (net (code "235") (name "Net-(rxPI1C-TYPEC0_SSRX2P)") (class "Default")
      (node (ref "J3") (pin "22") (pinfunction "22_22") (pintype "passive"))
      (node (ref "rxPI1") (pin "221") (pinfunction "TYPEC0_SSRX2P_221") (pintype "passive"))
    )
    (net (code "236") (name "Net-(rxPI1C-TYPEC0_SSTX1N)") (class "Default")
      (node (ref "J3") (pin "18") (pinfunction "18_18") (pintype "passive"))
      (node (ref "rxPI1") (pin "217") (pinfunction "TYPEC0_SSTX1N_217") (pintype "passive"))
    )
    (net (code "237") (name "Net-(rxPI1C-TYPEC0_SSTX1P)") (class "Default")
      (node (ref "J3") (pin "16") (pinfunction "16_16") (pintype "passive"))
      (node (ref "rxPI1") (pin "215") (pinfunction "TYPEC0_SSTX1P_215") (pintype "passive"))
    )
    (net (code "238") (name "Net-(rxPI1C-TYPEC0_SSTX2N)") (class "Default")
      (node (ref "J3") (pin "30") (pinfunction "30_30") (pintype "passive"))
      (node (ref "rxPI1") (pin "229") (pinfunction "TYPEC0_SSTX2N_229") (pintype "passive"))
    )
    (net (code "239") (name "Net-(rxPI1C-TYPEC0_SSTX2P)") (class "Default")
      (node (ref "J3") (pin "28") (pinfunction "28_28") (pintype "passive"))
      (node (ref "rxPI1") (pin "227") (pinfunction "TYPEC0_SSTX2P_227") (pintype "passive"))
    )
    (net (code "240") (name "Net-(rxPI1C-TYPEC5V_PWREN_H)") (class "Default")
      (node (ref "J3") (pin "96") (pinfunction "96_96") (pintype "passive"))
      (node (ref "rxPI1") (pin "295") (pinfunction "TYPEC5V_PWREN_H_295") (pintype "passive"))
    )
    (net (code "241") (name "Net-(rxPI1C-VCC_SD_3V3_S3)") (class "Default")
      (node (ref "J3") (pin "91") (pinfunction "91_91") (pintype "passive"))
      (node (ref "R3") (pin "2") (pinfunction "2_2") (pintype "passive"))
      (node (ref "rxPI1") (pin "292") (pinfunction "VCC_SD_3V3_S3_292") (pintype "passive"))
    )
    (net (code "242") (name "Net-(rxPI1C-WIFI_PWR_EN)") (class "Default")
      (node (ref "J3") (pin "23") (pinfunction "23_23") (pintype "passive"))
      (node (ref "rxPI1") (pin "224") (pinfunction "WIFI_PWR_EN_224") (pintype "passive"))
    )
    (net (code "243") (name "PCIe_CLK_N") (class "Default")
      (node (ref "H2") (pin "12") (pinfunction "12_12") (pintype "passive"))
      (node (ref "HB") (pin "11") (pinfunction "11_11") (pintype "passive"))
      (node (ref "rPI1") (pin "112") (pinfunction "PCIe_CLK_N_112") (pintype "passive"))
      (node (ref "rxPI1") (pin "112") (pinfunction "PCIe_CLK_N_112") (pintype "passive"))
    )
    (net (code "244") (name "PCIe_CLK_P") (class "Default")
      (node (ref "H2") (pin "10") (pinfunction "10_10") (pintype "passive"))
      (node (ref "HB") (pin "9") (pinfunction "9_9") (pintype "passive"))
      (node (ref "rPI1") (pin "110") (pinfunction "PCIe_CLK_P_110") (pintype "passive"))
      (node (ref "rxPI1") (pin "110") (pinfunction "PCIe_CLK_P_110") (pintype "passive"))
    )
    (net (code "245") (name "PCIe_CLK_nREQ") (class "Default")
      (node (ref "H2") (pin "2") (pinfunction "2_2") (pintype "passive"))
      (node (ref "HB") (pin "1") (pinfunction "1_1") (pintype "passive"))
      (node (ref "rPI1") (pin "102") (pinfunction "PCIe_CLK_nREQ_102") (pintype "passive"))
      (node (ref "rxPI1") (pin "102") (pinfunction "PCIe_CLK_nREQ_102") (pintype "passive"))
    )
    (net (code "246") (name "PCIe_RX_N") (class "Default")
      (node (ref "H2") (pin "18") (pinfunction "18_18") (pintype "passive"))
      (node (ref "HB") (pin "17") (pinfunction "17_17") (pintype "passive"))
      (node (ref "rPI1") (pin "118") (pinfunction "PCIe_RX_N_118") (pintype "passive"))
      (node (ref "rxPI1") (pin "118") (pinfunction "PCIe_RX_N_118") (pintype "passive"))
    )
    (net (code "247") (name "PCIe_RX_P") (class "Default")
      (node (ref "H2") (pin "16") (pinfunction "16_16") (pintype "passive"))
      (node (ref "HB") (pin "15") (pinfunction "15_15") (pintype "passive"))
      (node (ref "rPI1") (pin "116") (pinfunction "PCIe_RX_P_116") (pintype "passive"))
      (node (ref "rxPI1") (pin "116") (pinfunction "PCIe_RX_P_116") (pintype "passive"))
    )
    (net (code "248") (name "PCIe_TX_N") (class "Default")
      (node (ref "H2") (pin "24") (pinfunction "24_24") (pintype "passive"))
      (node (ref "HB") (pin "23") (pinfunction "23_23") (pintype "passive"))
      (node (ref "rPI1") (pin "124") (pinfunction "PCIe_TX_N_124") (pintype "passive"))
      (node (ref "rxPI1") (pin "124") (pinfunction "PCIe_TX_N_124") (pintype "passive"))
    )
    (net (code "249") (name "PCIe_TX_P") (class "Default")
      (node (ref "H2") (pin "22") (pinfunction "22_22") (pintype "passive"))
      (node (ref "HB") (pin "21") (pinfunction "21_21") (pintype "passive"))
      (node (ref "rPI1") (pin "122") (pinfunction "PCIe_TX_P_122") (pintype "passive"))
      (node (ref "rxPI1") (pin "122") (pinfunction "PCIe_TX_P_122") (pintype "passive"))
    )
    (net (code "250") (name "PCIe_nRST") (class "Default")
      (node (ref "H2") (pin "9") (pinfunction "9_9") (pintype "passive"))
      (node (ref "HB") (pin "10") (pinfunction "10_10") (pintype "passive"))
      (node (ref "rPI1") (pin "109") (pinfunction "PCIe_nRST_109") (pintype "passive"))
      (node (ref "rxPI1") (pin "109") (pinfunction "PCIe_nRST_109") (pintype "passive"))
    )
    (net (code "251") (name "PRG_CC1") (class "Default")
      (node (ref "J1") (pin "A5") (pinfunction "CC1_A5") (pintype "bidirectional"))
      (node (ref "U1") (pin "1") (pinfunction "CC2_1") (pintype "bidirectional"))
      (node (ref "U1") (pin "14") (pinfunction "CC2_14") (pintype "bidirectional"))
    )
    (net (code "252") (name "PRG_CC2") (class "Default")
      (node (ref "J1") (pin "B5") (pinfunction "CC2_B5") (pintype "bidirectional"))
      (node (ref "U1") (pin "10") (pinfunction "CC1_10") (pintype "bidirectional"))
      (node (ref "U1") (pin "11") (pinfunction "CC1_11") (pintype "bidirectional"))
    )
    (net (code "253") (name "RD_CC1") (class "Default")
      (node (ref "HB") (pin "98") (pinfunction "98_98") (pintype "passive"))
      (node (ref "rPI1") (pin "197") (pinfunction "GND_197") (pintype "passive"))
    )
    (net (code "254") (name "Res104") (class "Default")
      (node (ref "H2") (pin "4") (pinfunction "4_4") (pintype "passive"))
      (node (ref "HB") (pin "3") (pinfunction "3_3") (pintype "passive"))
      (node (ref "rPI1") (pin "104") (pinfunction "PCIE_nWAKE_104") (pintype "passive"))
      (node (ref "rxPI1") (pin "104") (pinfunction "Reserved_104") (pintype "passive"))
    )
    (net (code "255") (name "Res106") (class "Default")
      (node (ref "H2") (pin "6") (pinfunction "6_6") (pintype "passive"))
      (node (ref "HB") (pin "5") (pinfunction "5_5") (pintype "passive"))
      (node (ref "rPI1") (pin "106") (pinfunction "PCIE_PWR_EN_106") (pintype "passive"))
      (node (ref "rxPI1") (pin "106") (pinfunction "Reserved_106") (pintype "passive"))
    )
    (net (code "256") (name "USB3HOST_D_N") (class "Default")
      (node (ref "J3") (pin "48") (pinfunction "48_48") (pintype "passive"))
      (node (ref "U2") (pin "27") (pinfunction "USB_DM_UP_27") (pintype "bidirectional"))
      (node (ref "rxPI1") (pin "247") (pinfunction "USB20_HOST1_DM_247") (pintype "passive"))
    )
    (net (code "257") (name "USB3HOST_D_P") (class "Default")
      (node (ref "J3") (pin "46") (pinfunction "46_46") (pintype "passive"))
      (node (ref "U2") (pin "26") (pinfunction "USB_DP_UP_26") (pintype "bidirectional"))
      (node (ref "rxPI1") (pin "245") (pinfunction "USB20_HOST1_DP_245") (pintype "passive"))
    )
    (net (code "258") (name "USB3HOST_RX_N") (class "Default")
      (node (ref "C19") (pin "1") (pinfunction "1_1") (pintype "passive"))
      (node (ref "J3") (pin "60") (pinfunction "60_60") (pintype "passive"))
      (node (ref "rxPI1") (pin "259") (pinfunction "C42_-_RXN_259") (pintype "passive"))
    )
    (net (code "259") (name "USB3HOST_RX_P") (class "Default")
      (node (ref "C18") (pin "1") (pinfunction "1_1") (pintype "passive"))
      (node (ref "J3") (pin "58") (pinfunction "58_58") (pintype "passive"))
      (node (ref "rxPI1") (pin "257") (pinfunction "D42_-_RXP_257") (pintype "passive"))
    )
    (net (code "260") (name "USB3HOST_TX_N") (class "Default")
      (node (ref "J3") (pin "54") (pinfunction "54_54") (pintype "passive"))
      (node (ref "U2") (pin "31") (pinfunction "USB_SSRXM_UP_31") (pintype "input"))
      (node (ref "rxPI1") (pin "253") (pinfunction "D41_-_TXN_253") (pintype "passive"))
    )
    (net (code "261") (name "USB3HOST_TX_P") (class "Default")
      (node (ref "J3") (pin "52") (pinfunction "52_52") (pintype "passive"))
      (node (ref "U2") (pin "32") (pinfunction "USB_SSRXP_UP_32") (pintype "input"))
      (node (ref "rxPI1") (pin "251") (pinfunction "E41_-_TXP_251") (pintype "passive"))
    )
    (net (code "262") (name "USB20_N") (class "Default")
      (node (ref "HB") (pin "4") (pinfunction "4_4") (pintype "passive"))
      (node (ref "J3") (pin "66") (pinfunction "66_66") (pintype "passive"))
      (node (ref "rPI1") (pin "103") (pinfunction "USB2_N_103") (pintype "passive"))
      (node (ref "rxPI1") (pin "265") (pinfunction "USB20_HOST0_DM_265") (pintype "passive"))
    )
    (net (code "263") (name "USB20_P") (class "Default")
      (node (ref "HB") (pin "6") (pinfunction "6_6") (pintype "passive"))
      (node (ref "J3") (pin "64") (pinfunction "64_64") (pintype "passive"))
      (node (ref "rPI1") (pin "105") (pinfunction "USB2_P_105") (pintype "passive"))
      (node (ref "rxPI1") (pin "263") (pinfunction "USB20_HOST0_DP_263") (pintype "passive"))
    )
    (net (code "264") (name "USB30_D_N") (class "Default")
      (node (ref "HB") (pin "35") (pinfunction "35_35") (pintype "passive"))
      (node (ref "U2") (pin "42") (pinfunction "USB_DM_DN1_42") (pintype "bidirectional"))
      (node (ref "rPI1") (pin "136") (pinfunction "USB3-0-D_N_136") (pintype "passive"))
    )
    (net (code "265") (name "USB30_D_P") (class "Default")
      (node (ref "HB") (pin "33") (pinfunction "33_33") (pintype "passive"))
      (node (ref "U2") (pin "41") (pinfunction "USB_DP_DN1_41") (pintype "bidirectional"))
      (node (ref "rPI1") (pin "134") (pinfunction "USB3-0-D_P_134") (pintype "passive"))
    )
    (net (code "266") (name "USB30_RX_N") (class "Default")
      (node (ref "HB") (pin "27") (pinfunction "27_27") (pintype "passive"))
      (node (ref "U2") (pin "47") (pinfunction "USB_SSRXM_DN1_47") (pintype "input"))
      (node (ref "rPI1") (pin "128") (pinfunction "USB3-0-RX_N_128") (pintype "passive"))
    )
    (net (code "267") (name "USB30_RX_P") (class "Default")
      (node (ref "HB") (pin "29") (pinfunction "29_29") (pintype "passive"))
      (node (ref "U2") (pin "46") (pinfunction "USB_SSRXP_DN1_46") (pintype "input"))
      (node (ref "rPI1") (pin "130") (pinfunction "USB3-0-RX_P_130") (pintype "passive"))
    )
    (net (code "268") (name "USB30_TX_N") (class "Default")
      (node (ref "C21") (pin "1") (pinfunction "1_1") (pintype "passive"))
      (node (ref "HB") (pin "39") (pinfunction "39_39") (pintype "passive"))
      (node (ref "rPI1") (pin "140") (pinfunction "USB3-0-TX_N_140") (pintype "passive"))
    )
    (net (code "269") (name "USB30_TX_P") (class "Default")
      (node (ref "C20") (pin "1") (pinfunction "1_1") (pintype "passive"))
      (node (ref "HB") (pin "41") (pinfunction "41_41") (pintype "passive"))
      (node (ref "rPI1") (pin "142") (pinfunction "USB3-0-TX_P_142") (pintype "passive"))
    )
    (net (code "270") (name "USB31_D_N") (class "Default")
      (node (ref "HB") (pin "66") (pinfunction "66_66") (pintype "passive"))
      (node (ref "U2") (pin "15") (pinfunction "USB_DM_DN2_15") (pintype "bidirectional"))
      (node (ref "rPI1") (pin "165") (pinfunction "USB3-1-D_N_165") (pintype "passive"))
    )
    (net (code "271") (name "USB31_D_P") (class "Default")
      (node (ref "HB") (pin "64") (pinfunction "64_64") (pintype "passive"))
      (node (ref "U2") (pin "14") (pinfunction "USB_DP_DN2_14") (pintype "bidirectional"))
      (node (ref "rPI1") (pin "163") (pinfunction "USB3-1-D_P_163") (pintype "passive"))
    )
    (net (code "272") (name "USB31_RX_N") (class "Default")
      (node (ref "HB") (pin "58") (pinfunction "58_58") (pintype "passive"))
      (node (ref "U2") (pin "20") (pinfunction "USB_SSRXM_DN2_20") (pintype "input"))
      (node (ref "rPI1") (pin "157") (pinfunction "USB3-1-RX_N_157") (pintype "passive"))
    )
    (net (code "273") (name "USB31_RX_P") (class "Default")
      (node (ref "HB") (pin "60") (pinfunction "60_60") (pintype "passive"))
      (node (ref "U2") (pin "19") (pinfunction "USB_SSRXP_DN2_19") (pintype "input"))
      (node (ref "rPI1") (pin "159") (pinfunction "USB3-1-RX_P_159") (pintype "passive"))
    )
    (net (code "274") (name "USB31_TX_N") (class "Default")
      (node (ref "C23") (pin "1") (pinfunction "1_1") (pintype "passive"))
      (node (ref "HB") (pin "70") (pinfunction "70_70") (pintype "passive"))
      (node (ref "rPI1") (pin "169") (pinfunction "USB3-1-TX_N_169") (pintype "passive"))
    )
    (net (code "275") (name "USB31_TX_P") (class "Default")
      (node (ref "C22") (pin "1") (pinfunction "1_1") (pintype "passive"))
      (node (ref "HB") (pin "72") (pinfunction "72_72") (pintype "passive"))
      (node (ref "rPI1") (pin "171") (pinfunction "USB3-1-TX_P_171") (pintype "passive"))
    )
    (net (code "276") (name "USBP_D_N") (class "Default")
      (node (ref "D1") (pin "6") (pinfunction "I/O1_6") (pintype "bidirectional"))
      (node (ref "J1") (pin "A7") (pinfunction "DN1_A7") (pintype "bidirectional"))
      (node (ref "J1") (pin "B7") (pinfunction "DN2_B7") (pintype "bidirectional"))
    )
    (net (code "277") (name "USBP_D_P") (class "Default")
      (node (ref "D1") (pin "4") (pinfunction "I/O2_4") (pintype "bidirectional"))
      (node (ref "J1") (pin "A6") (pinfunction "DP1_A6") (pintype "bidirectional"))
      (node (ref "J1") (pin "B6") (pinfunction "DP2_B6") (pintype "bidirectional"))
    )
    (net (code "278") (name "USB_OTG_D_N") (class "Default")
      (node (ref "H2") (pin "3") (pinfunction "3_3") (pintype "passive"))
      (node (ref "L1") (pin "1") (pinfunction "1_1") (pintype "passive"))
      (node (ref "rxPI1") (pin "103") (pinfunction "USB2_N_103") (pintype "passive"))
    )
    (net (code "279") (name "USB_OTG_D_P") (class "Default")
      (node (ref "H2") (pin "5") (pinfunction "5_5") (pintype "passive"))
      (node (ref "L1") (pin "2") (pinfunction "2_2") (pintype "passive"))
      (node (ref "rxPI1") (pin "105") (pinfunction "USB2_P_105") (pintype "passive"))
    )
    (net (code "280") (name "USB_OTG_ID") (class "Default")
      (node (ref "H2") (pin "1") (pinfunction "1_1") (pintype "passive"))
      (node (ref "HB") (pin "2") (pinfunction "2_2") (pintype "passive"))
      (node (ref "rPI1") (pin "101") (pinfunction "USB_OTG_ID_101") (pintype "passive"))
      (node (ref "rxPI1") (pin "101") (pinfunction "USB_OTG_ID_101") (pintype "passive"))
    )
    (net (code "281") (name "VCC_3V3_S3") (class "Default")
      (node (ref "H1") (pin "84") (pinfunction "84_84") (pintype "passive"))
      (node (ref "HA") (pin "83") (pinfunction "83_83") (pintype "passive"))
      (node (ref "R2") (pin "2") (pinfunction "2_2") (pintype "passive"))
      (node (ref "R3") (pin "1") (pinfunction "1_1") (pintype "passive"))
      (node (ref "U1") (pin "3") (pinfunction "VDD_3") (pintype "power_in"))
      (node (ref "U1") (pin "4") (pinfunction "VDD_4") (pintype "power_in"))
      (node (ref "rPI1") (pin "84") (pinfunction "+3.3v_(Output)_84") (pintype "passive"))
      (node (ref "rxPI1") (pin "84") (pinfunction "+3.3v_(Output)_84") (pintype "passive"))
    )
    (net (code "282") (name "unconnected-(J1-SBU1-PadA8)") (class "Default")
      (node (ref "J1") (pin "A8") (pinfunction "SBU1_A8") (pintype "bidirectional"))
    )
    (net (code "283") (name "unconnected-(J1-SBU2-PadB8)") (class "Default")
      (node (ref "J1") (pin "B8") (pinfunction "SBU2_B8") (pintype "bidirectional"))
    )
    (net (code "284") (name "unconnected-(U2-FULLPWRMGMTZ{slash}SMBA1{slash}SS_UP-Pad36)") (class "Default")
      (node (ref "U2") (pin "36") (pinfunction "FULLPWRMGMTZ/SMBA1/SS_UP_36") (pintype "input"))
    )
    (net (code "285") (name "unconnected-(U2-OVERCUR1Z-Pad5)") (class "Default")
      (node (ref "U2") (pin "5") (pinfunction "OVERCUR1Z_5") (pintype "input"))
    )
    (net (code "286") (name "unconnected-(U2-OVERCUR2Z-Pad8)") (class "Default")
      (node (ref "U2") (pin "8") (pinfunction "OVERCUR2Z_8") (pintype "input"))
    )
    (net (code "287") (name "unconnected-(U2-PWRCTL1{slash}BATEN1-Pad4)") (class "Default")
      (node (ref "U2") (pin "4") (pinfunction "PWRCTL1/BATEN1_4") (pintype "bidirectional"))
    )
    (net (code "288") (name "unconnected-(U2-PWRCTL2{slash}BATEN2-Pad6)") (class "Default")
      (node (ref "U2") (pin "6") (pinfunction "PWRCTL2/BATEN2_6") (pintype "bidirectional"))
    )
    (net (code "289") (name "unconnected-(U2-SCL{slash}SMBCLK-Pad2)") (class "Default")
      (node (ref "U2") (pin "2") (pinfunction "SCL/SMBCLK_2") (pintype "bidirectional"))
    )
    (net (code "290") (name "unconnected-(U2-SDA{slash}SMBDAT-Pad3)") (class "Default")
      (node (ref "U2") (pin "3") (pinfunction "SDA/SMBDAT_3") (pintype "bidirectional"))
    )
    (net (code "291") (name "unconnected-(U2-SMBUSZ{slash}SS_DN2-Pad22)") (class "Default")
      (node (ref "U2") (pin "22") (pinfunction "SMBUSZ/SS_DN2_22") (pintype "input"))
    )
  )
)
